# NeuroStimDuino_v3.net
KiCad netlist of a schematic drawn in EAGLE
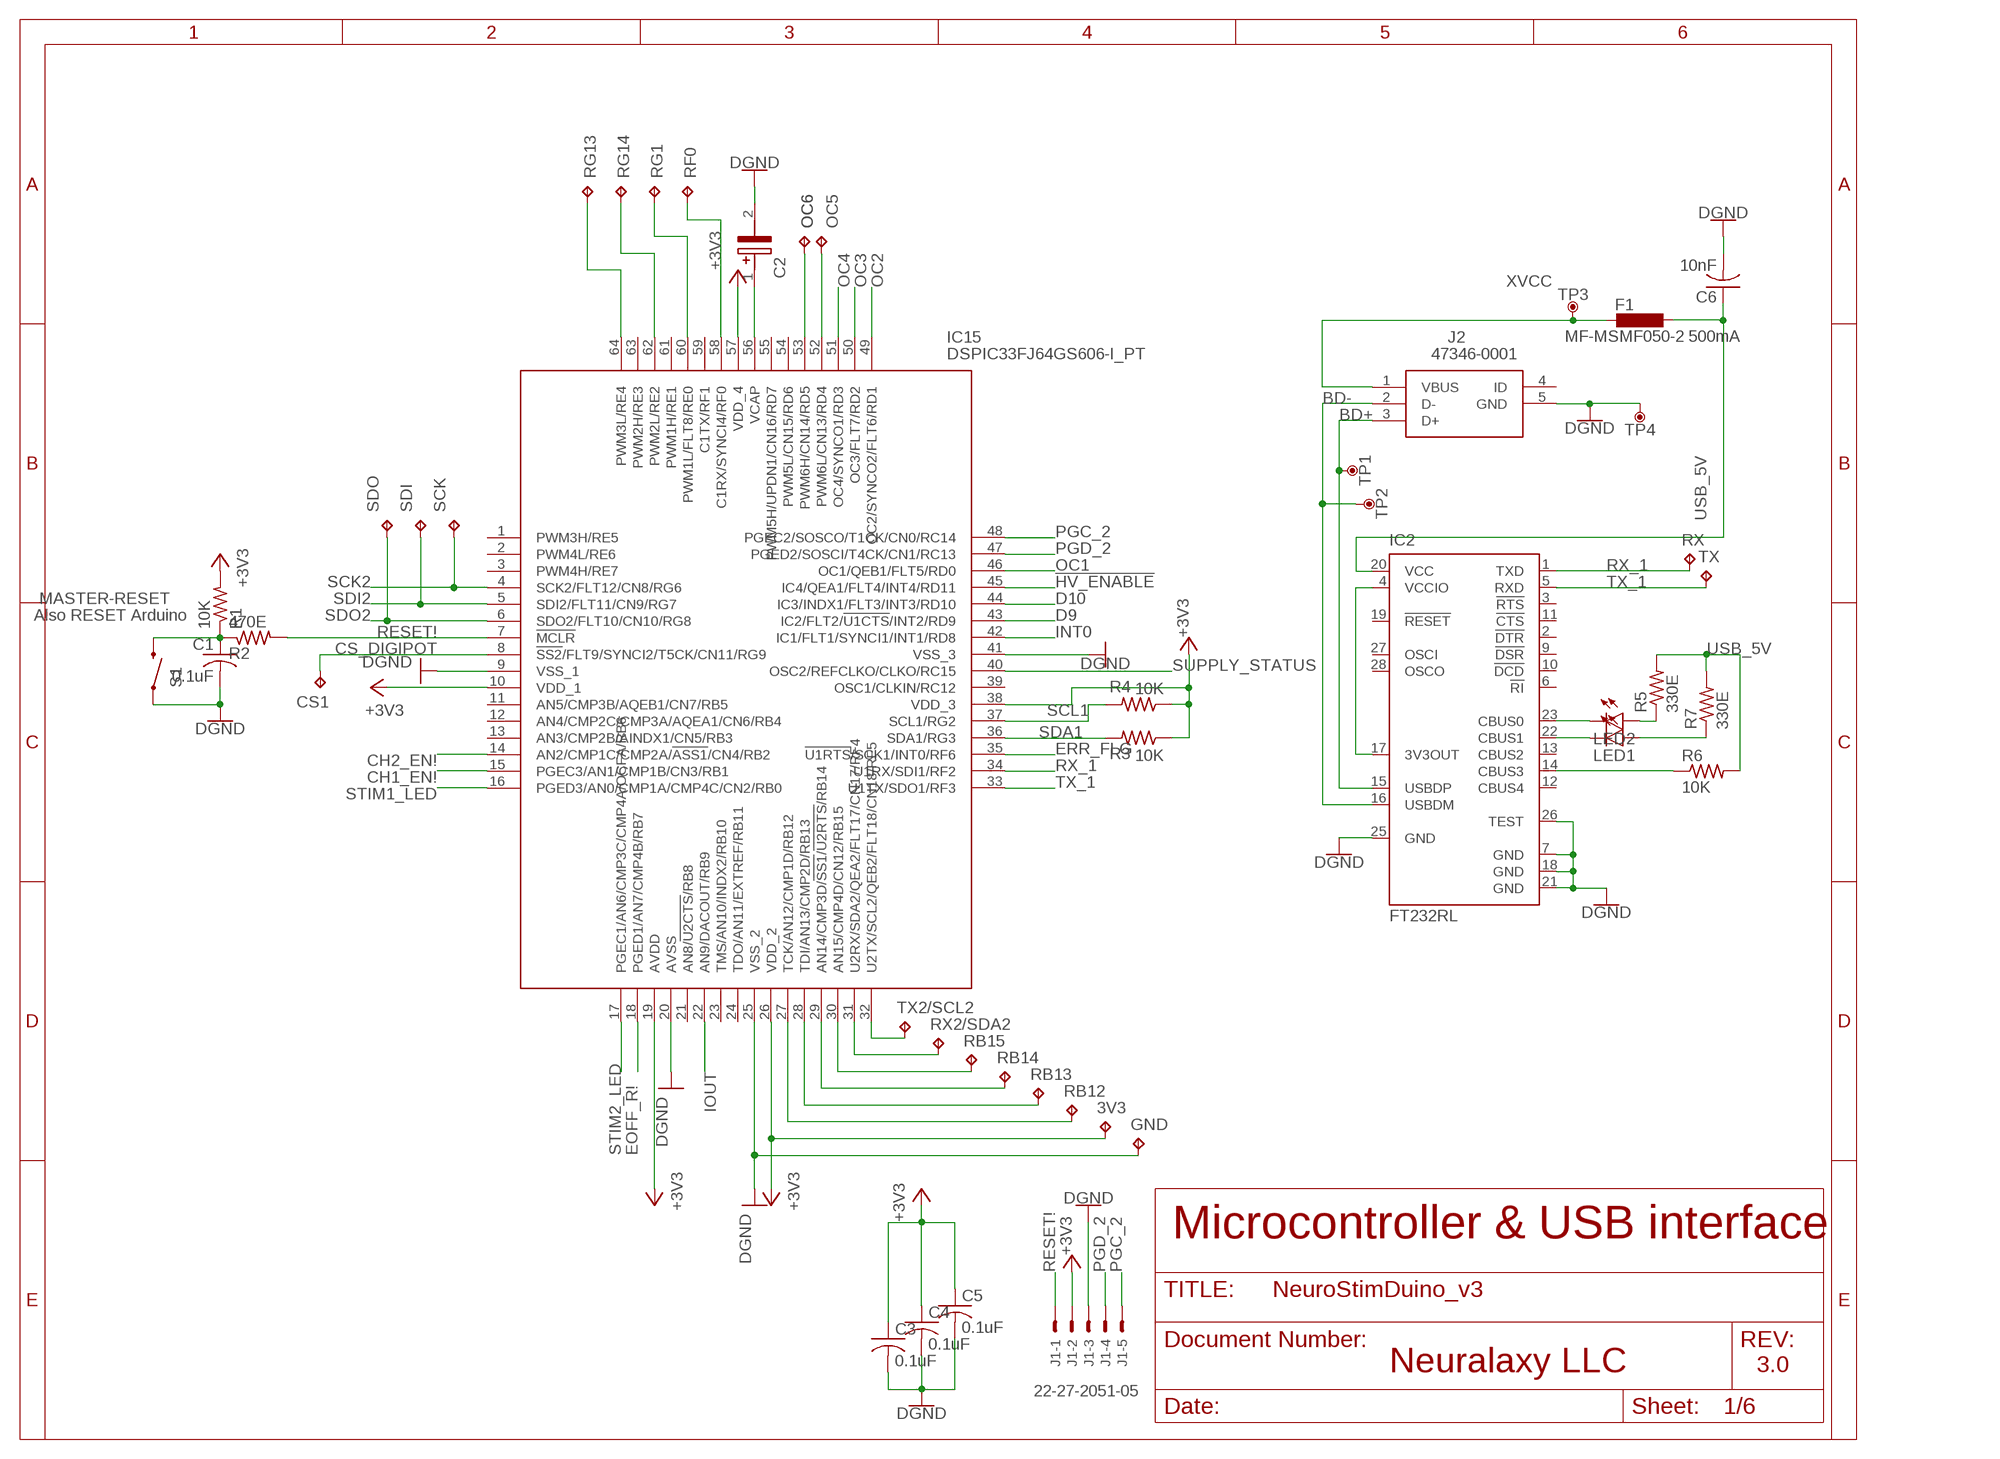
[diagram p0: schematic, sheet 1]
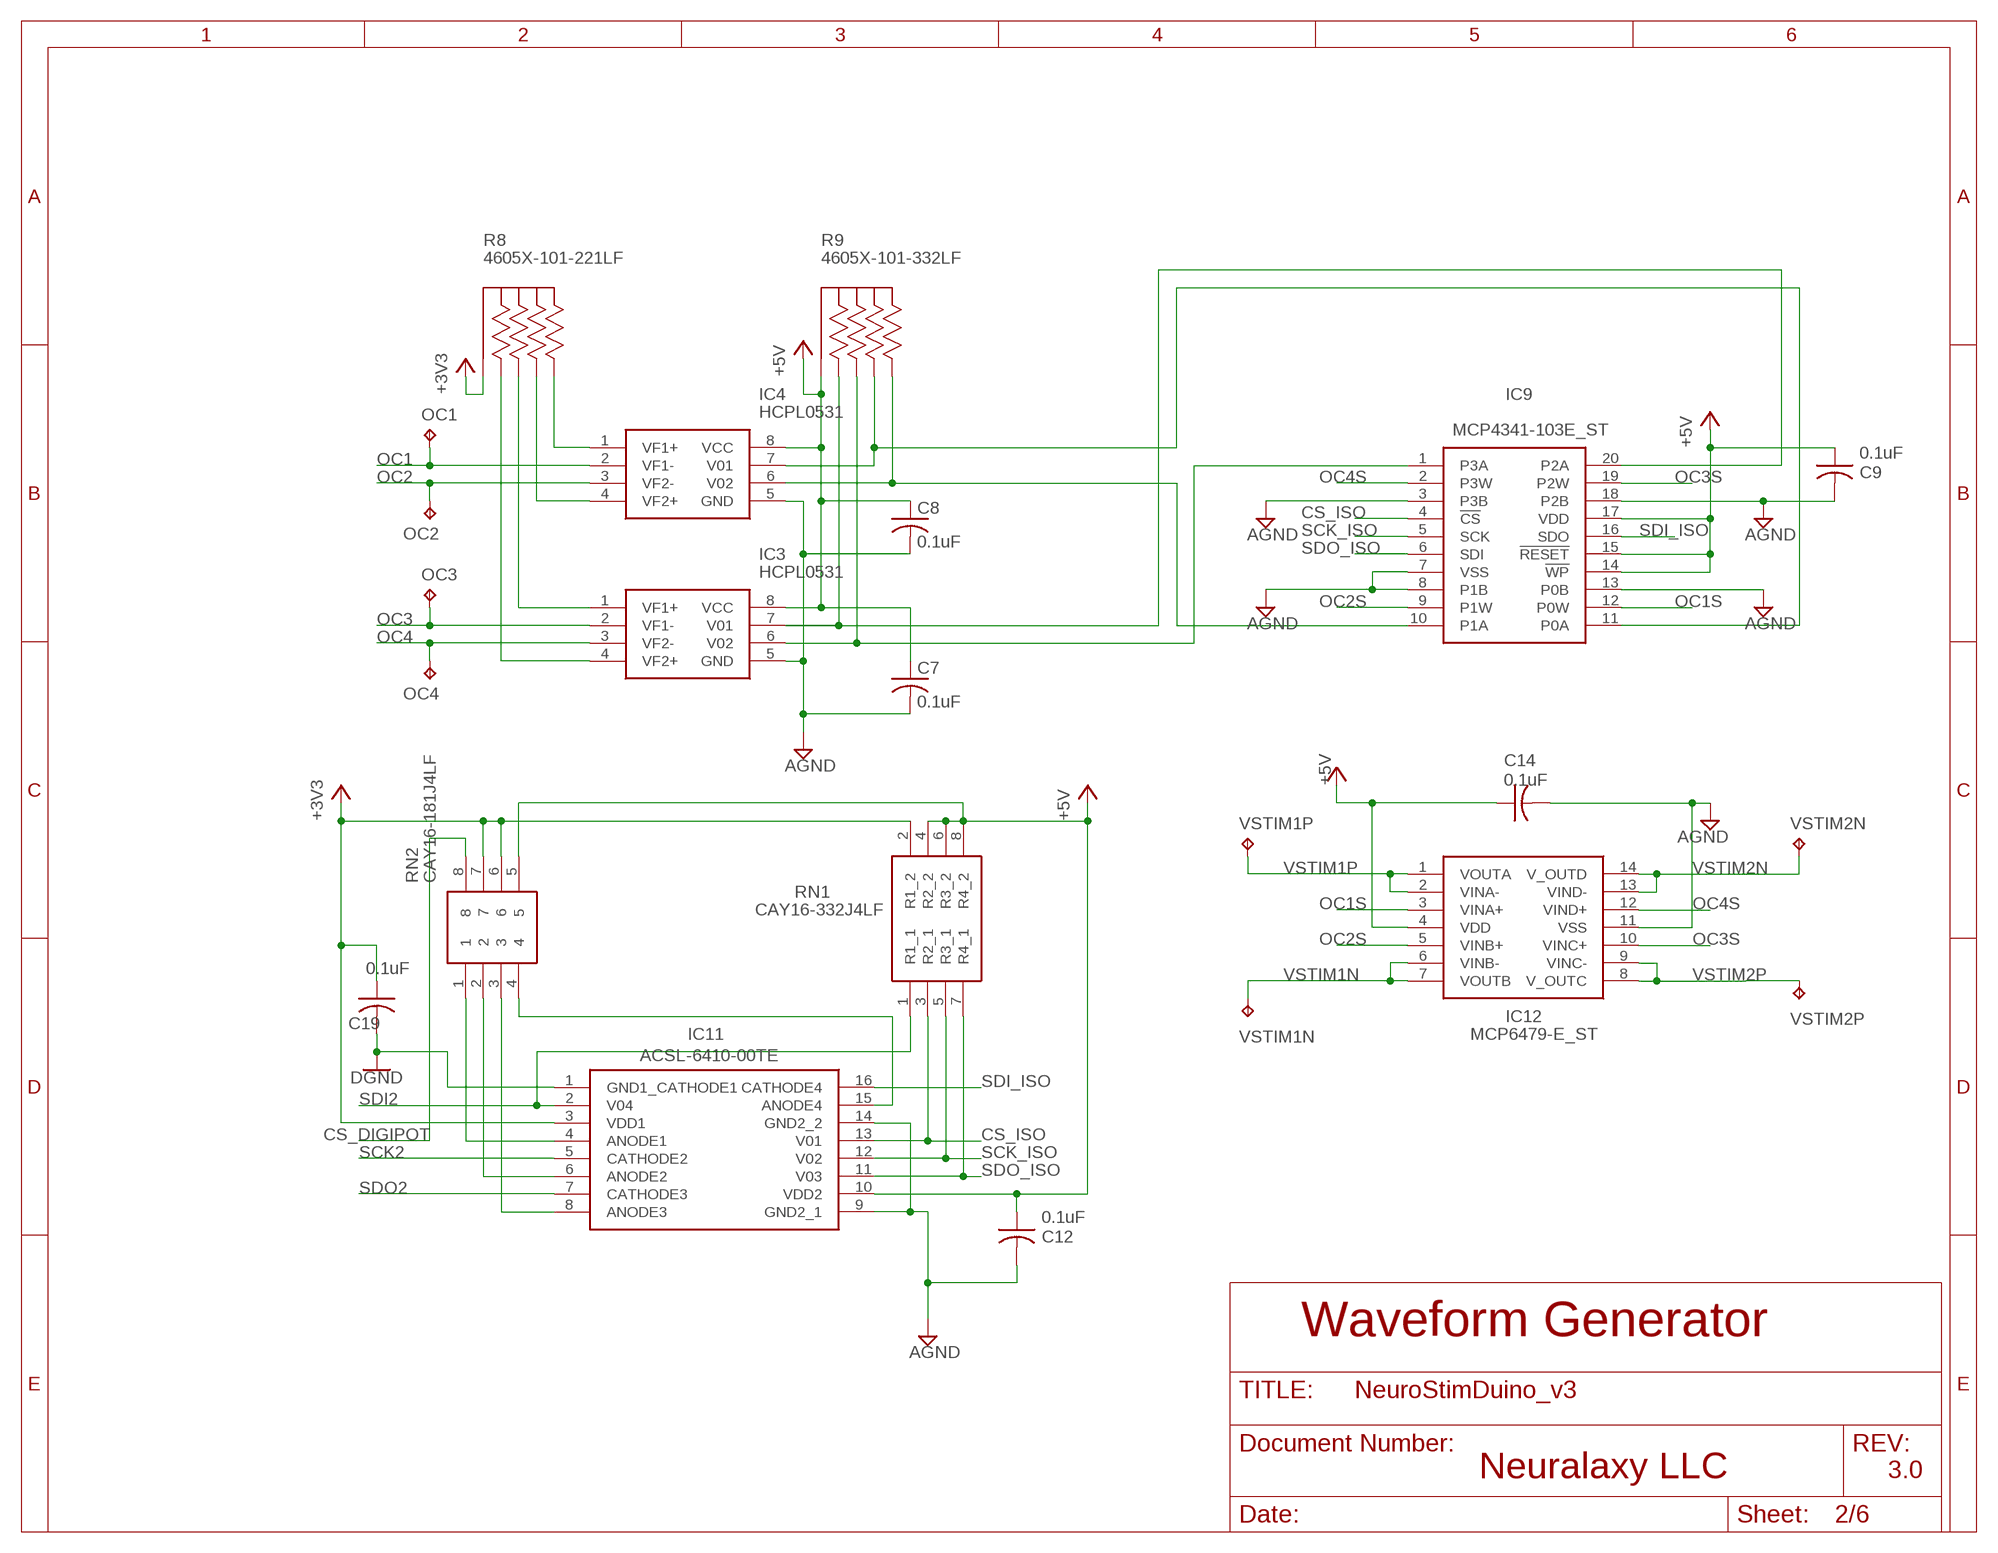
[diagram p1: schematic, sheet 2]
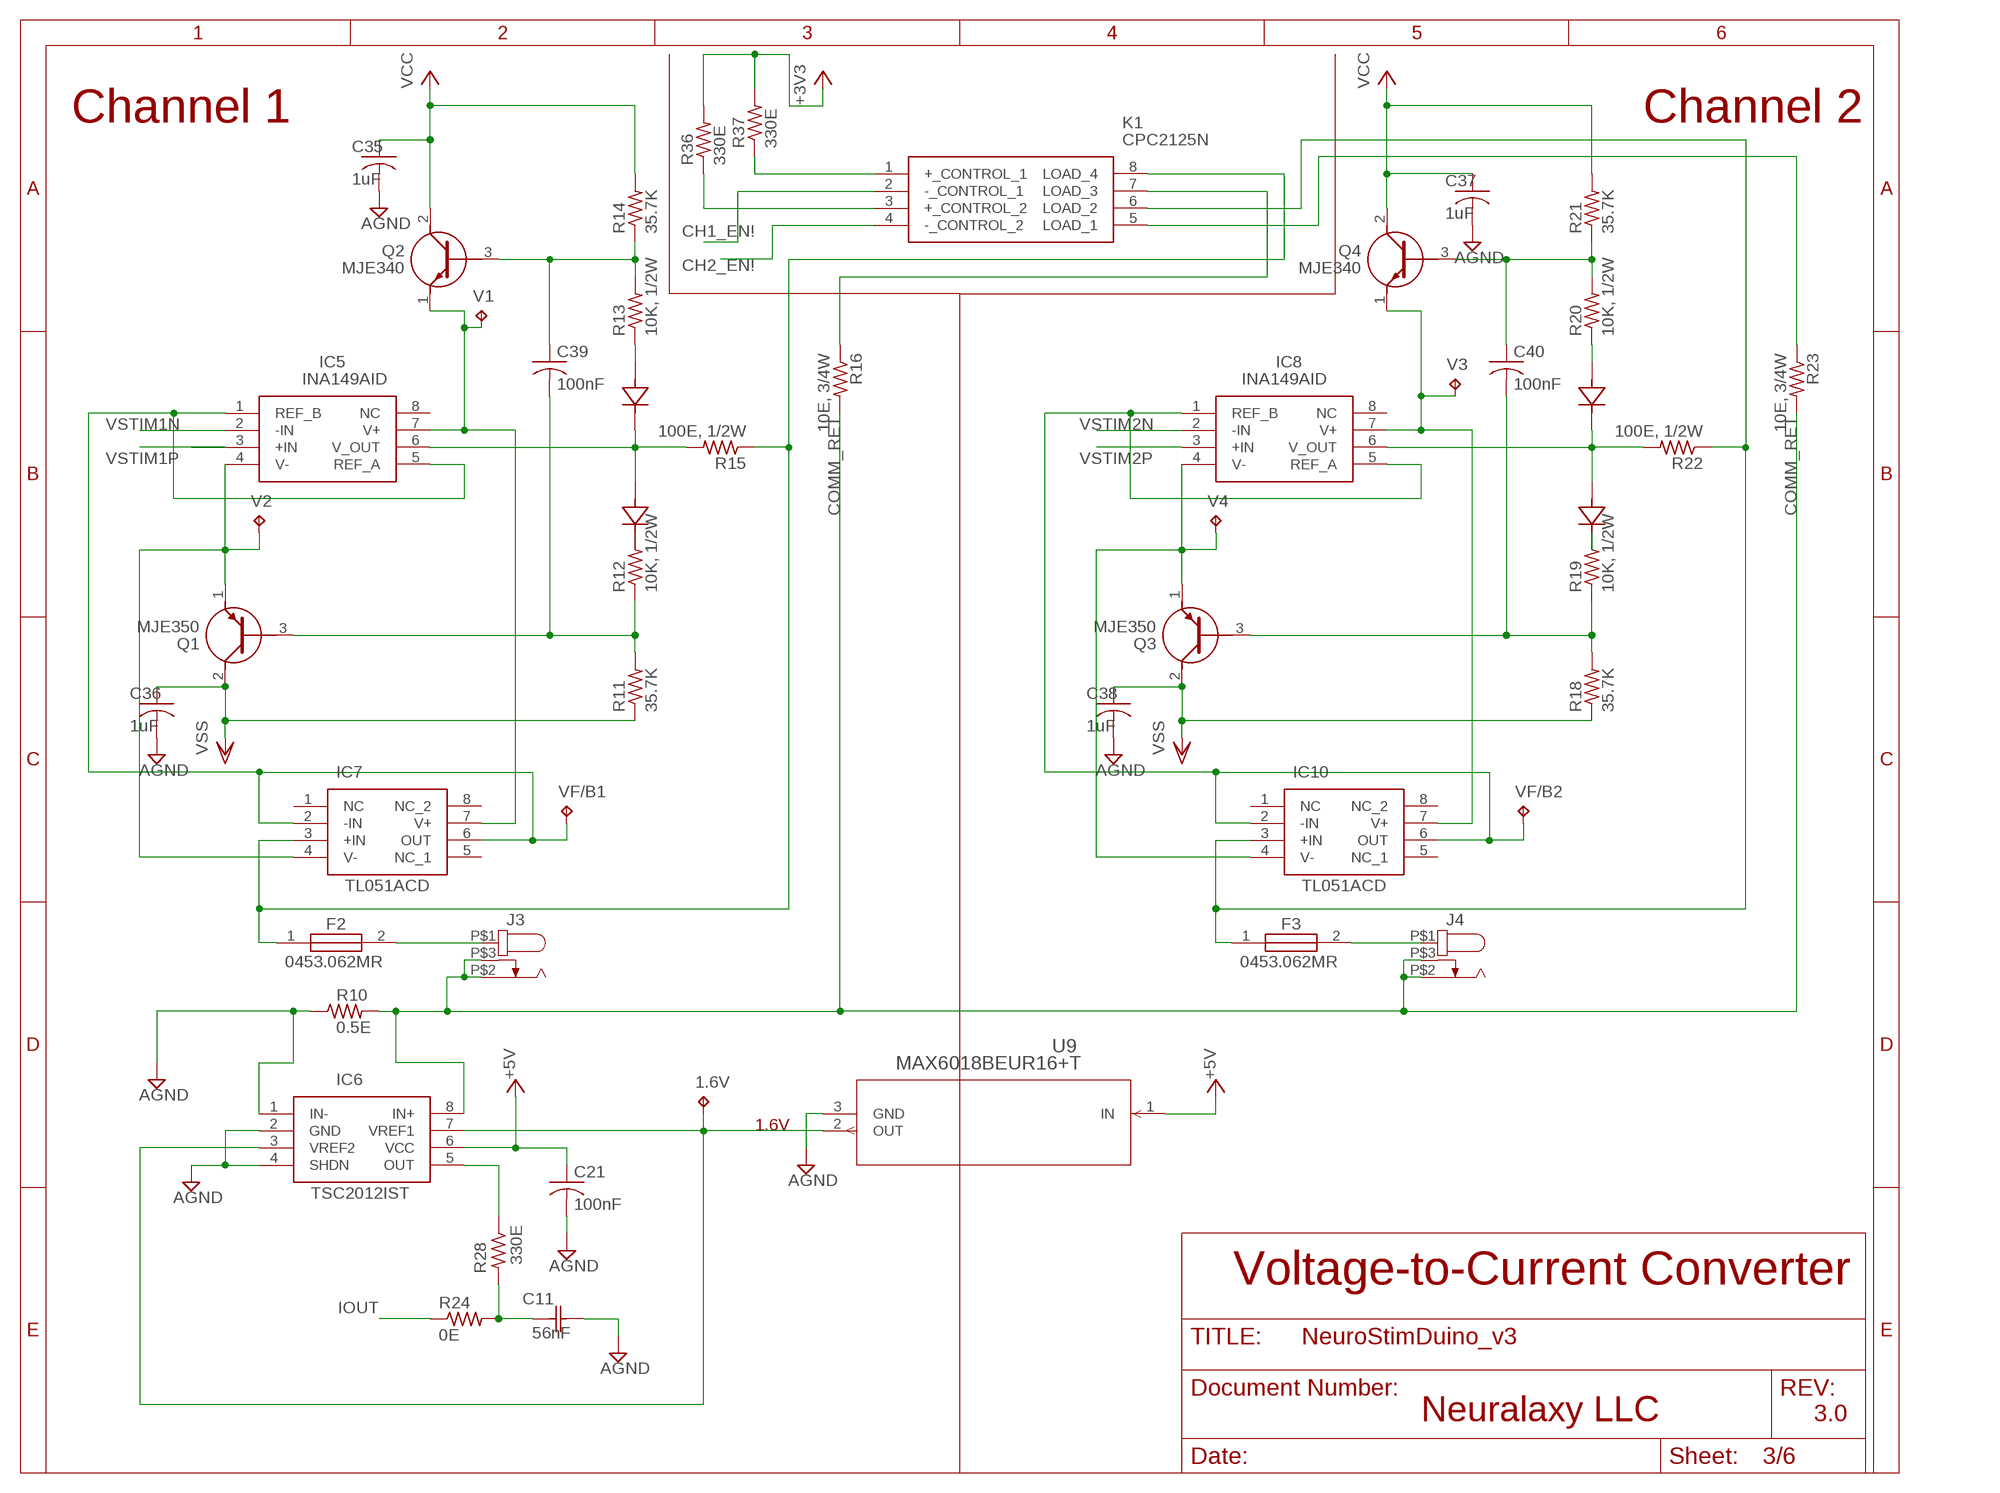
[diagram p2: schematic, sheet 3]
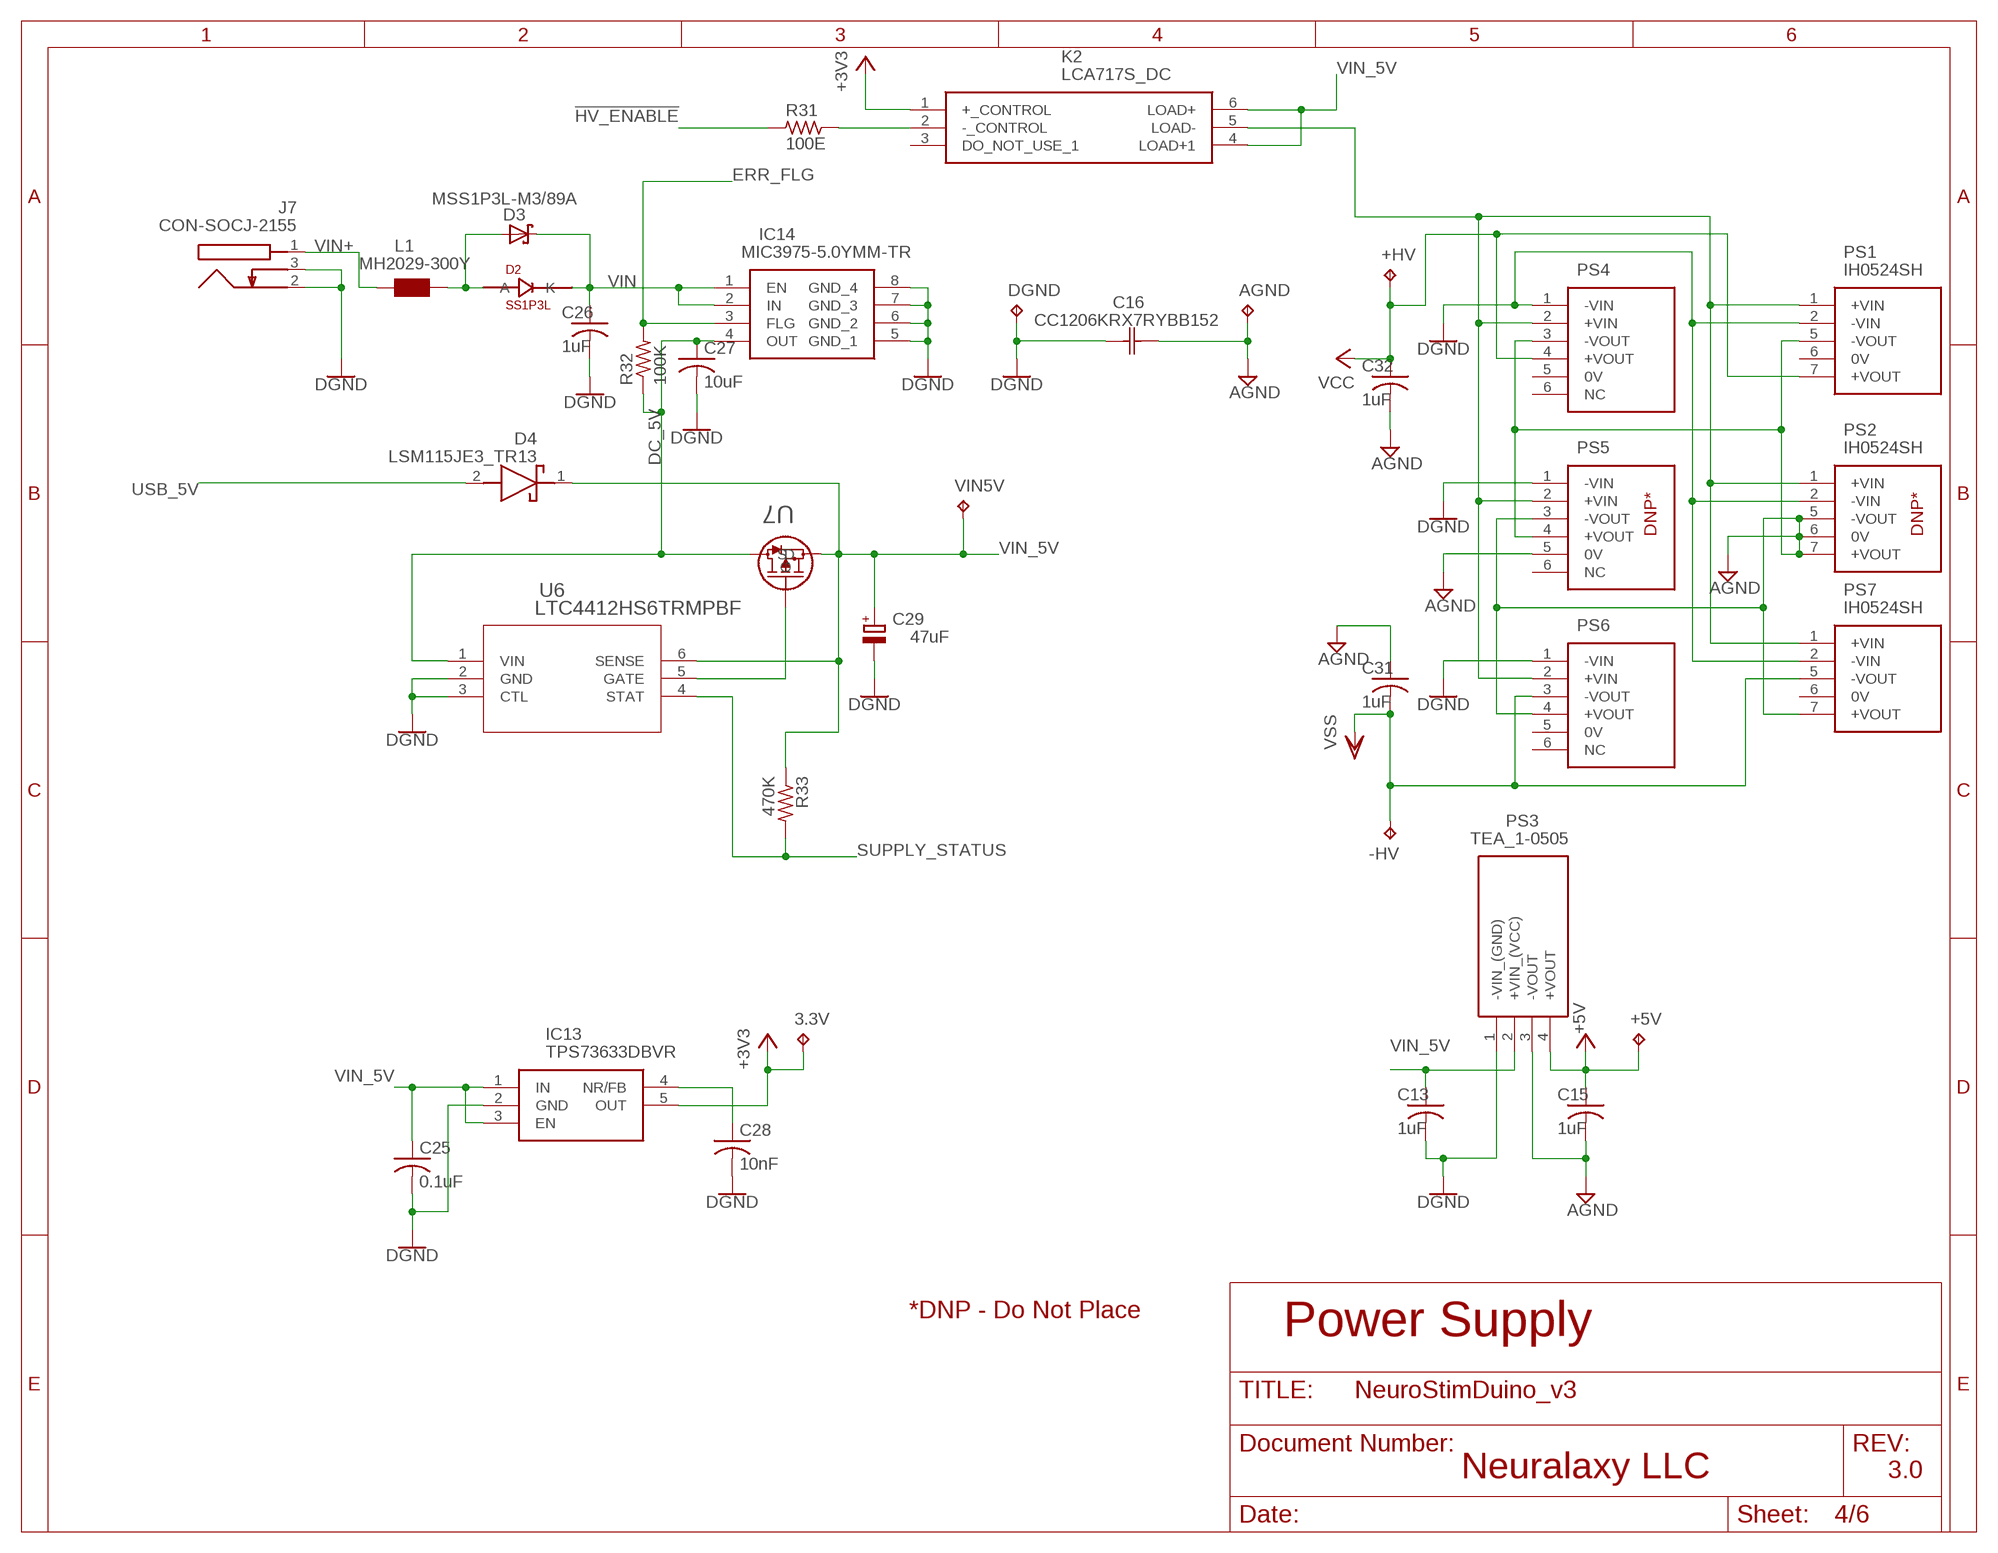
[diagram p3: schematic, sheet 4]
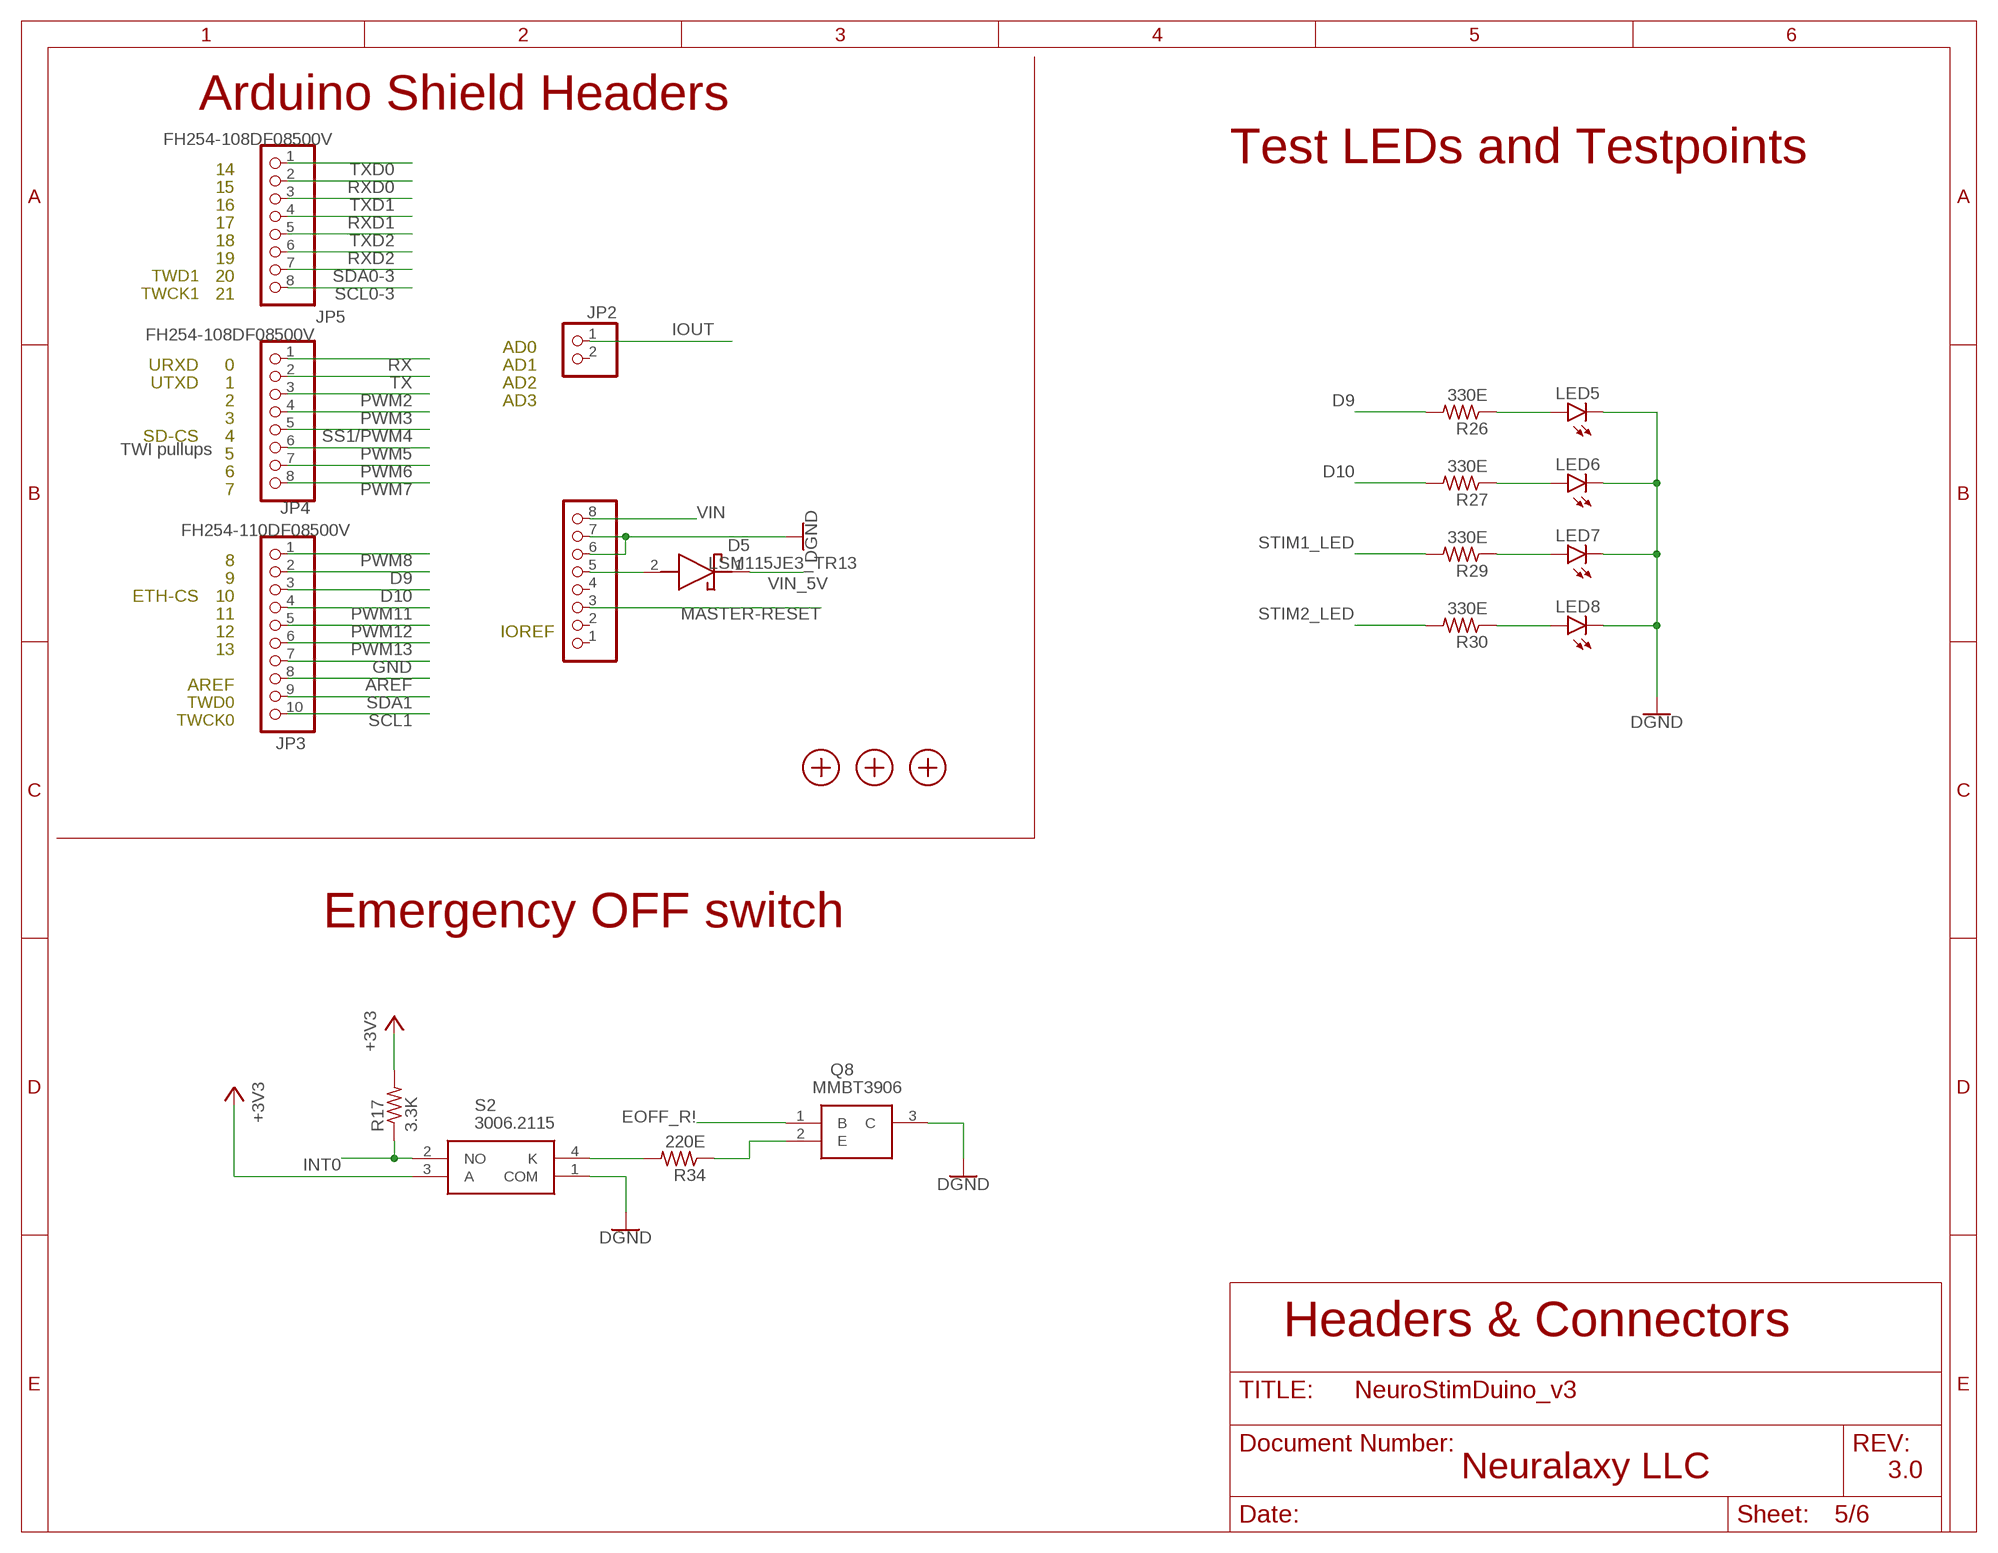
[diagram p4: schematic, sheet 5]
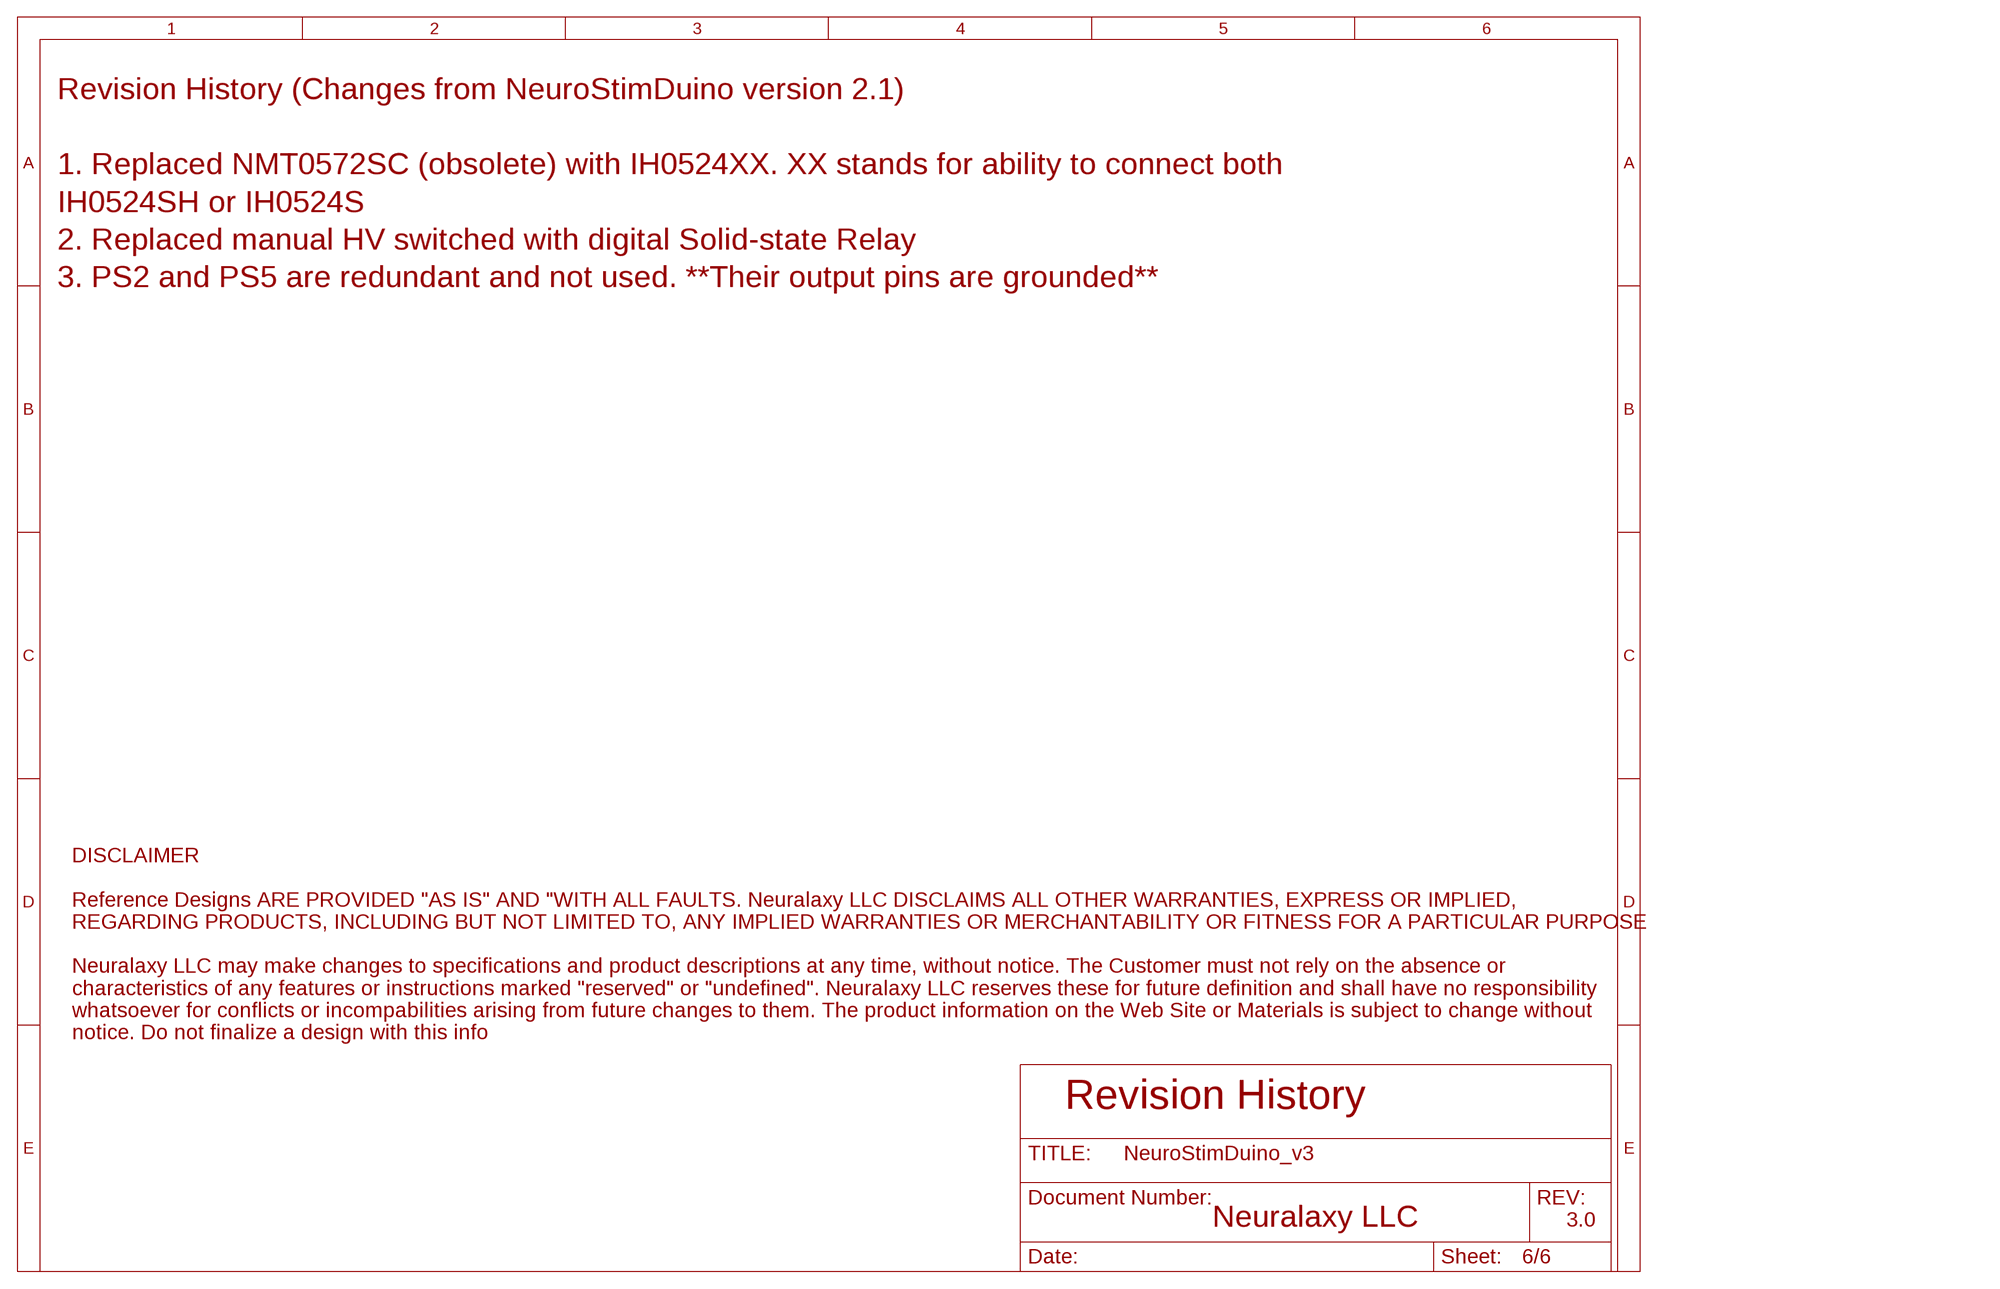
[diagram p5: schematic, sheet 6]

(export (version "E")
  (design (tool "Eeschema 10.0.6"))
  (components
    (comp (ref "1.6V")
      (value "TPTP10R")
      (footprint "eagle-import:TP10R")
      (libsource (lib "eagle-import") (part "TPTP10R"))
    )
    (comp (ref "C11")
      (value "56nF")
      (footprint "eagle-import:CAPC17595_87N_KEM")
      (fields (field (name "MANUFACTURER_PART_NUMBER") "C0603C563J4RACTU"))
      (libsource (lib "eagle-import") (part "C0603C563J4RACTU"))
    )
    (comp (ref "C21")
      (value "100nF")
      (footprint "eagle-import:C1206")
      (libsource (lib "eagle-import") (part "rcl_334_C-USC1206"))
    )
    (comp (ref "C35")
      (value "1uF")
      (footprint "eagle-import:C0805")
      (libsource (lib "eagle-import") (part "rcl_334_C-USC0805"))
    )
    (comp (ref "C36")
      (value "1uF")
      (footprint "eagle-import:C0805")
      (libsource (lib "eagle-import") (part "rcl_334_C-USC0805"))
    )
    (comp (ref "C37")
      (value "1uF")
      (footprint "eagle-import:C0805")
      (libsource (lib "eagle-import") (part "rcl_334_C-USC0805"))
    )
    (comp (ref "C38")
      (value "1uF")
      (footprint "eagle-import:C0805")
      (libsource (lib "eagle-import") (part "rcl_334_C-USC0805"))
    )
    (comp (ref "C39")
      (value "100nF")
      (footprint "eagle-import:C0805K")
      (libsource (lib "eagle-import") (part "rcl_334_C-USC0805K"))
    )
    (comp (ref "C40")
      (value "100nF")
      (footprint "eagle-import:C0805K")
      (libsource (lib "eagle-import") (part "rcl_334_C-USC0805K"))
    )
    (comp (ref "D6")
      (value "GF1J-E3DO-214BA-L")
      (footprint "eagle-import:DO-214BA-L")
      (fields (field (name "MANUFACTURER_PART_NUMBER") "GF1J-E3"))
      (libsource (lib "eagle-import") (part "GF1J-E3DO-214BA-L"))
    )
    (comp (ref "D7")
      (value "GF1J-E3DO-214BA-L")
      (footprint "eagle-import:DO-214BA-L")
      (fields (field (name "MANUFACTURER_PART_NUMBER") "GF1J-E3"))
      (libsource (lib "eagle-import") (part "GF1J-E3DO-214BA-L"))
    )
    (comp (ref "D8")
      (value "GF1J-E3DO-214BA-L")
      (footprint "eagle-import:DO-214BA-L")
      (fields (field (name "MANUFACTURER_PART_NUMBER") "GF1J-E3"))
      (libsource (lib "eagle-import") (part "GF1J-E3DO-214BA-L"))
    )
    (comp (ref "D9")
      (value "GF1J-E3DO-214BA-L")
      (footprint "eagle-import:DO-214BA-L")
      (fields (field (name "MANUFACTURER_PART_NUMBER") "GF1J-E3"))
      (libsource (lib "eagle-import") (part "GF1J-E3DO-214BA-L"))
    )
    (comp (ref "F2")
      (value "0453.062MR")
      (footprint "eagle-import:FUSC6127X294N")
      (libsource (lib "eagle-import") (part "0453.062MR"))
    )
    (comp (ref "F3")
      (value "0453.062MR")
      (footprint "eagle-import:FUSC6127X294N")
      (libsource (lib "eagle-import") (part "0453.062MR"))
    )
    (comp (ref "IC5")
      (value "INA149AID")
      (footprint "eagle-import:SOIC127P600X175-8N")
      (fields (field (name "MOUSER_PART_NUMBER") "595-INA149AID"))
      (libsource (lib "eagle-import") (part "INA149AID"))
    )
    (comp (ref "IC6")
      (value "TSC2012IST")
      (footprint "eagle-import:SOP65P490X110-8N")
      (fields
        (field (name "MANUFACTURER_PART_NUMBER") "TSC2011IST")
        (field (name "MOUSER_PART_NUMBER") "511-TSC2011IST")
      )
      (libsource (lib "eagle-import") (part "TSC2012IST"))
    )
    (comp (ref "IC7")
      (value "OPA140AID")
      (footprint "eagle-import:SOIC127P600X175-8N")
      (fields (field (name "MOUSER_PART_NUMBER") "595-OPA140AID"))
      (libsource (lib "eagle-import") (part "OPA140AID"))
    )
    (comp (ref "IC8")
      (value "INA149AID")
      (footprint "eagle-import:SOIC127P600X175-8N")
      (fields (field (name "MOUSER_PART_NUMBER") "595-INA149AID"))
      (libsource (lib "eagle-import") (part "INA149AID"))
    )
    (comp (ref "IC10")
      (value "OPA140AID")
      (footprint "eagle-import:SOIC127P600X175-8N")
      (fields (field (name "MOUSER_PART_NUMBER") "595-OPA140AID"))
      (libsource (lib "eagle-import") (part "OPA140AID"))
    )
    (comp (ref "J3")
      (value "DC_JACK_081BB-2103300")
      (footprint "eagle-import:081BB-2103300")
      (libsource (lib "eagle-import") (part "DC_JACK_081BB-2103300"))
    )
    (comp (ref "J4")
      (value "DC_JACK_081BB-2103300")
      (footprint "eagle-import:081BB-2103300")
      (libsource (lib "eagle-import") (part "DC_JACK_081BB-2103300"))
    )
    (comp (ref "K1")
      (value "CPC2125N")
      (footprint "eagle-import:SOP254P610X218-8N")
      (fields (field (name "MOUSER_PART_NUMBER") "849-CPC2125N"))
      (libsource (lib "eagle-import") (part "CPC2125N"))
    )
    (comp (ref "Q1")
      (value "MJE350")
      (footprint "eagle-import:TO229P300X760X1364-3P")
      (fields
        (field (name "MANUFACTURER_PART_NUMBER") "MJE350G")
        (field (name "MOUSER_PART_NUMBER") "863-MJE350G")
      )
      (libsource (lib "eagle-import") (part "MJE350"))
    )
    (comp (ref "Q2")
      (value "MJE340")
      (footprint "eagle-import:TO229P290X760X1320-3P")
      (fields (field (name "MOUSER_PART_NUMBER") "511-MJE340"))
      (libsource (lib "eagle-import") (part "MJE340"))
    )
    (comp (ref "Q3")
      (value "MJE350")
      (footprint "eagle-import:TO229P300X760X1364-3P")
      (fields
        (field (name "MANUFACTURER_PART_NUMBER") "MJE350G")
        (field (name "MOUSER_PART_NUMBER") "863-MJE350G")
      )
      (libsource (lib "eagle-import") (part "MJE350"))
    )
    (comp (ref "Q4")
      (value "MJE340")
      (footprint "eagle-import:TO229P290X760X1320-3P")
      (fields (field (name "MOUSER_PART_NUMBER") "511-MJE340"))
      (libsource (lib "eagle-import") (part "MJE340"))
    )
    (comp (ref "R10")
      (value "0.5E")
      (footprint "eagle-import:R1206")
      (libsource (lib "eagle-import") (part "rcl_334_R-US_R1206"))
    )
    (comp (ref "R11")
      (value "35.7K")
      (footprint "eagle-import:R1206")
      (libsource (lib "eagle-import") (part "rcl_334_R-US_R1206"))
    )
    (comp (ref "R12")
      (value "10K, 1/2W")
      (footprint "eagle-import:R1206")
      (libsource (lib "eagle-import") (part "rcl_334_R-US_R1206"))
    )
    (comp (ref "R13")
      (value "10K, 1/2W")
      (footprint "eagle-import:R1206")
      (libsource (lib "eagle-import") (part "rcl_334_R-US_R1206"))
    )
    (comp (ref "R14")
      (value "35.7K")
      (footprint "eagle-import:R1206")
      (libsource (lib "eagle-import") (part "rcl_334_R-US_R1206"))
    )
    (comp (ref "R15")
      (value "100E, 1/2W")
      (footprint "eagle-import:R1206")
      (libsource (lib "eagle-import") (part "rcl_334_R-US_R1206"))
    )
    (comp (ref "R16")
      (value "10E, 3/4W")
      (footprint "eagle-import:R1206")
      (libsource (lib "eagle-import") (part "rcl_334_R-US_R1206"))
    )
    (comp (ref "R18")
      (value "35.7K")
      (footprint "eagle-import:R1206")
      (libsource (lib "eagle-import") (part "rcl_334_R-US_R1206"))
    )
    (comp (ref "R19")
      (value "10K, 1/2W")
      (footprint "eagle-import:R1206")
      (libsource (lib "eagle-import") (part "rcl_334_R-US_R1206"))
    )
    (comp (ref "R20")
      (value "10K, 1/2W")
      (footprint "eagle-import:R1206")
      (libsource (lib "eagle-import") (part "rcl_334_R-US_R1206"))
    )
    (comp (ref "R21")
      (value "35.7K")
      (footprint "eagle-import:R1206")
      (libsource (lib "eagle-import") (part "rcl_334_R-US_R1206"))
    )
    (comp (ref "R22")
      (value "100E, 1/2W")
      (footprint "eagle-import:R1206")
      (libsource (lib "eagle-import") (part "rcl_334_R-US_R1206"))
    )
    (comp (ref "R23")
      (value "10E, 3/4W")
      (footprint "eagle-import:R1206")
      (libsource (lib "eagle-import") (part "rcl_334_R-US_R1206"))
    )
    (comp (ref "R24")
      (value "0E")
      (footprint "eagle-import:R1206")
      (libsource (lib "eagle-import") (part "rcl_334_R-US_R1206"))
    )
    (comp (ref "R28")
      (value "330E")
      (footprint "eagle-import:R0603")
      (libsource (lib "eagle-import") (part "R-US_R0603"))
    )
    (comp (ref "R36")
      (value "330E")
      (footprint "eagle-import:R1206")
      (libsource (lib "eagle-import") (part "R-US_R1206"))
    )
    (comp (ref "R37")
      (value "330E")
      (footprint "eagle-import:R1206")
      (libsource (lib "eagle-import") (part "R-US_R1206"))
    )
    (comp (ref "U9")
      (value "MAX6018BEUR16+T")
      (footprint "eagle-import:21-0051H_MXM")
      (libsource (lib "eagle-import") (part "MAX6018BEUR16+T"))
    )
    (comp (ref "V1")
      (value "TPTP10R")
      (footprint "eagle-import:TP10R")
      (libsource (lib "eagle-import") (part "TPTP10R"))
    )
    (comp (ref "V2")
      (value "TPTP10R")
      (footprint "eagle-import:TP10R")
      (libsource (lib "eagle-import") (part "TPTP10R"))
    )
    (comp (ref "V3")
      (value "TPTP10R")
      (footprint "eagle-import:TP10R")
      (libsource (lib "eagle-import") (part "TPTP10R"))
    )
    (comp (ref "V4")
      (value "TPTP10R")
      (footprint "eagle-import:TP10R")
      (libsource (lib "eagle-import") (part "TPTP10R"))
    )
    (comp (ref "VF/B1")
      (value "TPTP10R")
      (footprint "eagle-import:TP10R")
      (libsource (lib "eagle-import") (part "TPTP10R"))
    )
    (comp (ref "VF/B2")
      (value "TPTP10R")
      (footprint "eagle-import:TP10R")
      (libsource (lib "eagle-import") (part "TPTP10R"))
    )
    (comp (ref "+5V")
      (value "TPTP10R")
      (footprint "eagle-import:TP10R")
      (libsource (lib "eagle-import") (part "TPTP10R"))
    )
    (comp (ref "+HV")
      (value "TPTP10R")
      (footprint "eagle-import:TP10R")
      (libsource (lib "eagle-import") (part "TPTP10R"))
    )
    (comp (ref "-HV")
      (value "TPTP10R")
      (footprint "eagle-import:TP10R")
      (libsource (lib "eagle-import") (part "TPTP10R"))
    )
    (comp (ref "3.3V")
      (value "TPTP10R")
      (footprint "eagle-import:TP10R")
      (libsource (lib "eagle-import") (part "TPTP10R"))
    )
    (comp (ref "AGND")
      (value "TPTP10R")
      (footprint "eagle-import:TP10R")
      (libsource (lib "eagle-import") (part "TPTP10R"))
    )
    (comp (ref "C13")
      (value "1uF")
      (footprint "eagle-import:C0805")
      (libsource (lib "eagle-import") (part "rcl_334_C-USC0805"))
    )
    (comp (ref "C15")
      (value "1uF")
      (footprint "eagle-import:C0805")
      (libsource (lib "eagle-import") (part "rcl_334_C-USC0805"))
    )
    (comp (ref "C16")
      (value "CC1206KRX7RYBB152")
      (footprint "eagle-import:CAP_CC1206_YAG")
      (fields (field (name "COPYRIGHT") "Copyright (C) 2025 Ultra Librarian. All rights reserved."))
      (libsource (lib "eagle-import") (part "CC1206KRX7RYBB152"))
    )
    (comp (ref "C25")
      (value "0.1uF")
      (footprint "eagle-import:C1206")
      (libsource (lib "eagle-import") (part "C-USC1206"))
    )
    (comp (ref "C26")
      (value "1uF")
      (footprint "eagle-import:C0805")
      (libsource (lib "eagle-import") (part "rcl_334_C-USC0805"))
    )
    (comp (ref "C27")
      (value "10uF")
      (footprint "eagle-import:C0805")
      (libsource (lib "eagle-import") (part "rcl_334_C-USC0805"))
    )
    (comp (ref "C28")
      (value "10nF")
      (footprint "eagle-import:C1206")
      (libsource (lib "eagle-import") (part "C-USC1206"))
    )
    (comp (ref "C29")
      (value "47uF")
      (footprint "eagle-import:PANASONIC_D")
      (libsource (lib "eagle-import") (part "0113_47UF"))
    )
    (comp (ref "C31")
      (value "1uF")
      (footprint "eagle-import:C0805")
      (libsource (lib "eagle-import") (part "rcl_334_C-USC0805"))
    )
    (comp (ref "C32")
      (value "1uF")
      (footprint "eagle-import:C0805")
      (libsource (lib "eagle-import") (part "rcl_334_C-USC0805"))
    )
    (comp (ref "D2")
      (value "SS1P3L")
      (footprint "eagle-import:DO220AAL")
      (fields (field (name "PART_NUMBER") "SS1P3L-M3/84A"))
      (libsource (lib "eagle-import") (part "0025_SS1P3L-M3/84A"))
    )
    (comp (ref "D3")
      (value "MSS1P3L-M3/89A")
      (footprint "eagle-import:MICROSMP")
      (libsource (lib "eagle-import") (part "1653_MSS1P3L-M3/89A"))
    )
    (comp (ref "D4")
      (value "LSM115JE3_TR13")
      (footprint "eagle-import:DIOM5436X330N")
      (fields
        (field (name "ARROW_PART_NUMBER") "LSM115JE3/TR13")
        (field (name "MOUSER_PART_NUMBER") "494-LSM115JE3/TR13")
      )
      (libsource (lib "eagle-import") (part "LSM115JE3_TR13"))
    )
    (comp (ref "DGND")
      (value "TPTP10R")
      (footprint "eagle-import:TP10R")
      (libsource (lib "eagle-import") (part "TPTP10R"))
    )
    (comp (ref "IC13")
      (value "TPS73633DBVR")
      (footprint "eagle-import:SOT95P280X145-5N")
      (fields (field (name "MOUSER_PART_NUMBER") "595-TPS73633DBVR"))
      (libsource (lib "eagle-import") (part "TPS73633DBVR"))
    )
    (comp (ref "IC14")
      (value "MIC3975-5.0YMM-TR")
      (footprint "eagle-import:SOP65P490X109-8N")
      (libsource (lib "eagle-import") (part "MIC3975-5.0YMM-TR"))
    )
    (comp (ref "J7")
      (value "CON-SOCJ-2155")
      (footprint "eagle-import:CONSOCJ2155")
      (fields (field (name "MOUSER_PART_NUMBER") "992-CON-SOCJ-2155"))
      (libsource (lib "eagle-import") (part "CON-SOCJ-2155"))
    )
    (comp (ref "K2")
      (value "LCA717S_DC")
      (footprint "eagle-import:SOP254P952X470-6N")
      (fields
        (field (name "MANUFACTURER_PART_NUMBER") "LCA717S")
        (field (name "MOUSER_PART_NUMBER") "849-LCA717S")
      )
      (libsource (lib "eagle-import") (part "LCA717S_DC"))
    )
    (comp (ref "L1")
      (value "MH2029-300Y")
      (footprint "eagle-import:0805")
      (fields (field (name "PART_NUMBER") "BLM21PG300SN1D_/_MH2029-300Y"))
      (libsource (lib "eagle-import") (part "0001_BLM21PG300SN1D_/_MH2029-300Y"))
    )
    (comp (ref "PS1")
      (value "IH0524SH")
      (footprint "eagle-import:IH0524SH")
      (fields (field (name "MOUSER_PART_NUMBER") "209-IH0524SH"))
      (libsource (lib "eagle-import") (part "IH0524SH"))
    )
    (comp (ref "PS2")
      (value "IH0524SH")
      (footprint "eagle-import:IH0524SH")
      (fields (field (name "MOUSER_PART_NUMBER") "209-IH0524SH"))
      (libsource (lib "eagle-import") (part "IH0524SH"))
    )
    (comp (ref "PS3")
      (value "TEA_1-0505")
      (footprint "eagle-import:TEA10505")
      (fields
        (field (name "MANUFACTURER_PART_NUMBER") "TEA 1-0505")
        (field (name "MOUSER_PART_NUMBER") "495-TEA1-0505")
      )
      (libsource (lib "eagle-import") (part "TEA_1-0505"))
    )
    (comp (ref "PS4")
      (value "IH0524D")
      (footprint "eagle-import:IH0524D")
      (libsource (lib "eagle-import") (part "IH0524D"))
    )
    (comp (ref "PS5")
      (value "IH0524D")
      (footprint "eagle-import:IH0524D")
      (libsource (lib "eagle-import") (part "IH0524D"))
    )
    (comp (ref "PS6")
      (value "IH0524D")
      (footprint "eagle-import:IH0524D")
      (libsource (lib "eagle-import") (part "IH0524D"))
    )
    (comp (ref "PS7")
      (value "IH0524SH")
      (footprint "eagle-import:IH0524SH")
      (fields (field (name "MOUSER_PART_NUMBER") "209-IH0524SH"))
      (libsource (lib "eagle-import") (part "IH0524SH"))
    )
    (comp (ref "R31")
      (value "100E")
      (footprint "eagle-import:R0805")
      (libsource (lib "eagle-import") (part "R_0805"))
    )
    (comp (ref "R32")
      (value "100K")
      (footprint "eagle-import:R1206")
      (libsource (lib "eagle-import") (part "rcl_334_R-US_R1206"))
    )
    (comp (ref "R33")
      (value "470K")
      (footprint "eagle-import:R1206")
      (libsource (lib "eagle-import") (part "rcl_334_R-US_R1206"))
    )
    (comp (ref "U6")
      (value "LTC4412HS6TRMPBF")
      (footprint "eagle-import:TSOT-23_S6_ADI")
      (fields
        (field (name "MANUFACTURER_PART_NUMBER") "LTC4412HS6#TRMPBF")
        (field (name "COPYRIGHT") "Copyright (C) 2018 Accelerated Designs. All rights reserved")
      )
      (libsource (lib "eagle-import") (part "LTC4412HS6TRMPBF"))
    )
    (comp (ref "U7")
      (value "PMV48XP,215TO-236_SOT23_NEX-L")
      (footprint "eagle-import:TO-236_SOT23_NEX-L")
      (fields
        (field (name "MANUFACTURER_PART_NUMBER") "PMV48XP,215")
        (field (name "COPYRIGHT") "Copyright (C) 2018 Accelerated Designs. All rights reserved")
      )
      (libsource (lib "eagle-import") (part "PMV48XP,215TO-236_SOT23_NEX-L"))
    )
    (comp (ref "VIN5V")
      (value "TPTP10R")
      (footprint "eagle-import:TP10R")
      (libsource (lib "eagle-import") (part "TPTP10R"))
    )
    (comp (ref "C7")
      (value "0.1uF")
      (footprint "eagle-import:C1206")
      (libsource (lib "eagle-import") (part "rcl_334_C-USC1206"))
    )
    (comp (ref "C8")
      (value "0.1uF")
      (footprint "eagle-import:C1206")
      (libsource (lib "eagle-import") (part "rcl_334_C-USC1206"))
    )
    (comp (ref "C9")
      (value "0.1uF")
      (footprint "eagle-import:C1206")
      (libsource (lib "eagle-import") (part "rcl_334_C-USC1206"))
    )
    (comp (ref "C12")
      (value "0.1uF")
      (footprint "eagle-import:C1206")
      (libsource (lib "eagle-import") (part "rcl_334_C-USC1206"))
    )
    (comp (ref "C14")
      (value "0.1uF")
      (footprint "eagle-import:C1206")
      (libsource (lib "eagle-import") (part "rcl_334_C-USC1206"))
    )
    (comp (ref "C19")
      (value "0.1uF")
      (footprint "eagle-import:C1206")
      (libsource (lib "eagle-import") (part "rcl_334_C-USC1206"))
    )
    (comp (ref "IC3")
      (value "HCPL0531")
      (footprint "eagle-import:SOIC127P594X363-8N")
      (fields (field (name "MOUSER_PART_NUMBER") "512-HCPL0531"))
      (libsource (lib "eagle-import") (part "HCPL0531"))
    )
    (comp (ref "IC4")
      (value "HCPL0531")
      (footprint "eagle-import:SOIC127P594X363-8N")
      (fields (field (name "MOUSER_PART_NUMBER") "512-HCPL0531"))
      (libsource (lib "eagle-import") (part "HCPL0531"))
    )
    (comp (ref "IC9")
      (value "MCP4341-103E_ST")
      (footprint "eagle-import:SOP65P640X120-20N")
      (fields
        (field (name "MANUFACTURER_PART_NUMBER") "MCP4341-103E/ST")
        (field (name "MOUSER_PART_NUMBER") "579-MCP4341103E/ST")
      )
      (libsource (lib "eagle-import") (part "MCP4341-103E_ST"))
    )
    (comp (ref "IC11")
      (value "ACSL-6410-00TE")
      (footprint "eagle-import:SOIC127P599X152-16N")
      (fields (field (name "MOUSER_PART_NUMBER") "630-ACSL-6410-00TE"))
      (libsource (lib "eagle-import") (part "ACSL-6410-00TE"))
    )
    (comp (ref "IC12")
      (value "MCP6479-E_ST")
      (footprint "eagle-import:SOP65P640X120-14N")
      (fields
        (field (name "MANUFACTURER_PART_NUMBER") "MCP6479-E/ST")
        (field (name "MOUSER_PART_NUMBER") "579-MCP6479-E/ST")
      )
      (libsource (lib "eagle-import") (part "MCP6479-E_ST"))
    )
    (comp (ref "OC1")
      (value "TPTP08R")
      (footprint "eagle-import:TP08R")
      (libsource (lib "eagle-import") (part "TPTP08R"))
    )
    (comp (ref "OC2")
      (value "TPTP08R")
      (footprint "eagle-import:TP08R")
      (libsource (lib "eagle-import") (part "TPTP08R"))
    )
    (comp (ref "OC3")
      (value "TPTP10R")
      (footprint "eagle-import:TP10R")
      (libsource (lib "eagle-import") (part "TPTP10R"))
    )
    (comp (ref "OC4")
      (value "TPTP10R")
      (footprint "eagle-import:TP10R")
      (libsource (lib "eagle-import") (part "TPTP10R"))
    )
    (comp (ref "R8")
      (value "4605X-101-221LF")
      (footprint "eagle-import:BO_4605X")
      (fields (field (name "MANUFACTURER_PART_NUMBER") "4605X-101-222LF"))
      (libsource (lib "eagle-import") (part "4605X-101-221LF"))
    )
    (comp (ref "R9")
      (value "4605X-101-332LF")
      (footprint "eagle-import:BO_4605X")
      (fields (field (name "MANUFACTURER_PART_NUMBER") "4605X-101-222LF"))
      (libsource (lib "eagle-import") (part "4605X-101-332LF"))
    )
    (comp (ref "RN1")
      (value "CAY16-332J4LF")
      (footprint "eagle-import:CAY16-J4")
      (fields (field (name "MOUSER_PART_NUMBER") "652-CAY16-332J4LF"))
      (libsource (lib "eagle-import") (part "CAY16-332J4LF"))
    )
    (comp (ref "RN2")
      (value "CAY16-181J4LF")
      (footprint "eagle-import:CAY16181J4LF")
      (fields (field (name "MOUSER_PART_NUMBER") "652-CAY16-181J4LF"))
      (libsource (lib "eagle-import") (part "CAY16-181J4LF"))
    )
    (comp (ref "VSTIM1N")
      (value "TPTP08R")
      (footprint "eagle-import:TP08R")
      (libsource (lib "eagle-import") (part "TPTP08R"))
    )
    (comp (ref "VSTIM1P")
      (value "TPTP08R")
      (footprint "eagle-import:TP08R")
      (libsource (lib "eagle-import") (part "TPTP08R"))
    )
    (comp (ref "VSTIM2N")
      (value "TPTP08R")
      (footprint "eagle-import:TP08R")
      (libsource (lib "eagle-import") (part "TPTP08R"))
    )
    (comp (ref "VSTIM2P")
      (value "TPTP08R")
      (footprint "eagle-import:TP08R")
      (libsource (lib "eagle-import") (part "TPTP08R"))
    )
    (comp (ref "D5")
      (value "LSM115JE3_TR13")
      (footprint "eagle-import:DIOM5436X330N")
      (fields
        (field (name "ARROW_PART_NUMBER") "LSM115JE3/TR13")
        (field (name "MOUSER_PART_NUMBER") "494-LSM115JE3/TR13")
      )
      (libsource (lib "eagle-import") (part "LSM115JE3_TR13"))
    )
    (comp (ref "JP2")
      (value "PINHD-1X2")
      (footprint "eagle-import:1X02")
      (libsource (lib "eagle-import") (part "PINHD-1X2"))
    )
    (comp (ref "JP3")
      (value "FH254-110DF08500V")
      (footprint "eagle-import:1X10")
      (fields (field (name "PART_NUMBER") "20TW-537"))
      (libsource (lib "eagle-import") (part "1684_20TW-537"))
    )
    (comp (ref "JP4")
      (value "FH254-108DF08500V")
      (footprint "eagle-import:1X08")
      (fields (field (name "PART_NUMBER") "20TW-536"))
      (libsource (lib "eagle-import") (part "1683_20TW-536"))
    )
    (comp (ref "JP5")
      (value "FH254-108DF08500V")
      (footprint "eagle-import:1X08")
      (fields (field (name "PART_NUMBER") "20TW-536"))
      (libsource (lib "eagle-import") (part "1683_20TW-536"))
    )
    (comp (ref "JP6")
      (value "FH254-108DF08500V")
      (footprint "eagle-import:1X08")
      (fields (field (name "PART_NUMBER") "20TW-536"))
      (libsource (lib "eagle-import") (part "1683_20TW-536"))
    )
    (comp (ref "LED5")
      (value "LEDCHIPLED_1206")
      (footprint "eagle-import:CHIPLED_1206")
      (libsource (lib "eagle-import") (part "LEDCHIPLED_1206"))
    )
    (comp (ref "LED6")
      (value "LEDCHIPLED_1206")
      (footprint "eagle-import:CHIPLED_1206")
      (libsource (lib "eagle-import") (part "LEDCHIPLED_1206"))
    )
    (comp (ref "LED7")
      (value "LEDCHIPLED_1206")
      (footprint "eagle-import:CHIPLED_1206")
      (libsource (lib "eagle-import") (part "LEDCHIPLED_1206"))
    )
    (comp (ref "LED8")
      (value "LEDCHIPLED_1206")
      (footprint "eagle-import:CHIPLED_1206")
      (libsource (lib "eagle-import") (part "LEDCHIPLED_1206"))
    )
    (comp (ref "Q8")
      (value "MMBT3906")
      (footprint "eagle-import:SOT95P240X120-3N")
      (fields (field (name "MOUSER_PART_NUMBER") "512-MMBT3906"))
      (libsource (lib "eagle-import") (part "MMBT3906"))
    )
    (comp (ref "R17")
      (value "3.3K")
      (footprint "eagle-import:R1206")
      (libsource (lib "eagle-import") (part "rcl_334_R-US_R1206"))
    )
    (comp (ref "R26")
      (value "330E")
      (footprint "eagle-import:R0603")
      (libsource (lib "eagle-import") (part "R-US_R0603"))
    )
    (comp (ref "R27")
      (value "330E")
      (footprint "eagle-import:R0603")
      (libsource (lib "eagle-import") (part "R-US_R0603"))
    )
    (comp (ref "R29")
      (value "330E")
      (footprint "eagle-import:R0603")
      (libsource (lib "eagle-import") (part "R-US_R0603"))
    )
    (comp (ref "R30")
      (value "330E")
      (footprint "eagle-import:R0603")
      (libsource (lib "eagle-import") (part "R-US_R0603"))
    )
    (comp (ref "R34")
      (value "220E")
      (footprint "eagle-import:R1206")
      (libsource (lib "eagle-import") (part "rcl_334_R-US_R1206"))
    )
    (comp (ref "S2")
      (value "3006.2115")
      (footprint "eagle-import:30062115")
      (fields (field (name "MOUSER_PART_NUMBER") "979-3006.2115"))
      (libsource (lib "eagle-import") (part "3006.2115"))
    )
    (comp (ref "U$1")
      (value "FIDUCIALMOUNT")
      (footprint "eagle-import:FIDUCIA-MOUNT")
      (libsource (lib "eagle-import") (part "FIDUCIALMOUNT"))
    )
    (comp (ref "U$2")
      (value "FIDUCIALMOUNT")
      (footprint "eagle-import:FIDUCIA-MOUNT")
      (libsource (lib "eagle-import") (part "FIDUCIALMOUNT"))
    )
    (comp (ref "U$3")
      (value "FIDUCIALMOUNT")
      (footprint "eagle-import:FIDUCIA-MOUNT")
      (libsource (lib "eagle-import") (part "FIDUCIALMOUNT"))
    )
    (comp (ref "/OC5")
      (value "TPTP08R")
      (footprint "eagle-import:TP08R")
      (libsource (lib "eagle-import") (part "TPTP08R"))
    )
    (comp (ref "3V3")
      (value "TPTP08R")
      (footprint "eagle-import:TP08R")
      (libsource (lib "eagle-import") (part "TPTP08R"))
    )
    (comp (ref "C1")
      (value "0.1uF")
      (footprint "eagle-import:C0805")
      (libsource (lib "eagle-import") (part "C-USC0805"))
    )
    (comp (ref "C2")
      (value "F971C475MAAHT3")
      (footprint "eagle-import:CAPPM3216X180N")
      (fields (field (name "MOUSER_PART_NUMBER") "581-F971C475MAAHT3"))
      (libsource (lib "eagle-import") (part "F971C475MAAHT3"))
    )
    (comp (ref "C3")
      (value "0.1uF")
      (footprint "eagle-import:C1206")
      (libsource (lib "eagle-import") (part "C-USC1206"))
    )
    (comp (ref "C4")
      (value "0.1uF")
      (footprint "eagle-import:C1206")
      (libsource (lib "eagle-import") (part "C-USC1206"))
    )
    (comp (ref "C5")
      (value "0.1uF")
      (footprint "eagle-import:C1206")
      (libsource (lib "eagle-import") (part "C-USC1206"))
    )
    (comp (ref "C6")
      (value "10nF")
      (footprint "eagle-import:C1206")
      (libsource (lib "eagle-import") (part "rcl_334_C-USC1206"))
    )
    (comp (ref "CS1")
      (value "TPTP08R")
      (footprint "eagle-import:TP08R")
      (libsource (lib "eagle-import") (part "TPTP08R"))
    )
    (comp (ref "F1")
      (value "MF-MSMF050-2 500mA")
      (footprint "eagle-import:L1812")
      (fields (field (name "PART_NUMBER") "MF-MSMF050-2"))
      (libsource (lib "eagle-import") (part "0002_MF-MSMF050-2"))
    )
    (comp (ref "GND")
      (value "TPTP08R")
      (footprint "eagle-import:TP08R")
      (libsource (lib "eagle-import") (part "TPTP08R"))
    )
    (comp (ref "IC2")
      (value "FT232RL")
      (footprint "eagle-import:SSOP28")
      (libsource (lib "eagle-import") (part "FT232RL"))
    )
    (comp (ref "IC15")
      (value "DSPIC33FJ64GS606-I_PT")
      (footprint "eagle-import:QFP50P1200X1200X120-64N")
      (fields
        (field (name "MANUFACTURER_PART_NUMBER") "DSPIC33FJ64GS606-I/PT")
        (field (name "MOUSER_PART_NUMBER") "579-33FJ64GS606-I/PT")
      )
      (libsource (lib "eagle-import") (part "DSPIC33FJ64GS606-I_PT"))
    )
    (comp (ref "J1")
      (value "22-27-2051-05")
      (footprint "eagle-import:6410-05")
      (fields (field (name "MF") "MOLEX"))
      (libsource (lib "eagle-import") (part "22-?-0527-2051"))
    )
    (comp (ref "J2")
      (value "47346-0001")
      (footprint "eagle-import:47346-0001")
      (fields (field (name "MOUSER_PART_NUMBER") "538-47346-0001"))
      (libsource (lib "eagle-import") (part "47346-0001"))
    )
    (comp (ref "LED1")
      (value "LEDCHIPLED_1206")
      (footprint "eagle-import:CHIPLED_1206")
      (libsource (lib "eagle-import") (part "LEDCHIPLED_1206"))
    )
    (comp (ref "LED2")
      (value "LEDCHIPLED_1206")
      (footprint "eagle-import:CHIPLED_1206")
      (libsource (lib "eagle-import") (part "LEDCHIPLED_1206"))
    )
    (comp (ref "OC6")
      (value "TPTP08R")
      (footprint "eagle-import:TP08R")
      (libsource (lib "eagle-import") (part "TPTP08R"))
    )
    (comp (ref "R1")
      (value "10K")
      (footprint "eagle-import:R0805")
      (libsource (lib "eagle-import") (part "R-US_R0805"))
    )
    (comp (ref "R2")
      (value "470E")
      (footprint "eagle-import:R0805")
      (libsource (lib "eagle-import") (part "R-US_R0805"))
    )
    (comp (ref "R3")
      (value "10K")
      (footprint "eagle-import:R1206")
      (libsource (lib "eagle-import") (part "R-US_R1206"))
    )
    (comp (ref "R4")
      (value "10K")
      (footprint "eagle-import:R1206")
      (libsource (lib "eagle-import") (part "R-US_R1206"))
    )
    (comp (ref "R5")
      (value "330E")
      (footprint "eagle-import:R1206")
      (libsource (lib "eagle-import") (part "R-US_R1206"))
    )
    (comp (ref "R6")
      (value "10K")
      (footprint "eagle-import:R1206")
      (libsource (lib "eagle-import") (part "R-US_R1206"))
    )
    (comp (ref "R7")
      (value "330E")
      (footprint "eagle-import:R1206")
      (libsource (lib "eagle-import") (part "R-US_R1206"))
    )
    (comp (ref "RB12")
      (value "TPTP08R")
      (footprint "eagle-import:TP08R")
      (libsource (lib "eagle-import") (part "TPTP08R"))
    )
    (comp (ref "RB13")
      (value "TPTP08R")
      (footprint "eagle-import:TP08R")
      (libsource (lib "eagle-import") (part "TPTP08R"))
    )
    (comp (ref "RB14")
      (value "TPTP08R")
      (footprint "eagle-import:TP08R")
      (libsource (lib "eagle-import") (part "TPTP08R"))
    )
    (comp (ref "RB15")
      (value "TPTP08R")
      (footprint "eagle-import:TP08R")
      (libsource (lib "eagle-import") (part "TPTP08R"))
    )
    (comp (ref "RF0")
      (value "TPTP08R")
      (footprint "eagle-import:TP08R")
      (libsource (lib "eagle-import") (part "TPTP08R"))
    )
    (comp (ref "RG1")
      (value "TPTP08R")
      (footprint "eagle-import:TP08R")
      (libsource (lib "eagle-import") (part "TPTP08R"))
    )
    (comp (ref "RG13")
      (value "TPTP08R")
      (footprint "eagle-import:TP08R")
      (libsource (lib "eagle-import") (part "TPTP08R"))
    )
    (comp (ref "RG14")
      (value "TPTP08R")
      (footprint "eagle-import:TP08R")
      (libsource (lib "eagle-import") (part "TPTP08R"))
    )
    (comp (ref "RX")
      (value "TPTP20R")
      (footprint "eagle-import:TP20R")
      (libsource (lib "eagle-import") (part "TPTP20R"))
    )
    (comp (ref "RX2/SDA2")
      (value "TPTP08R")
      (footprint "eagle-import:TP08R")
      (libsource (lib "eagle-import") (part "TPTP08R"))
    )
    (comp (ref "S1")
      (value "SWITCH-MOMENTARY-2SMD")
      (footprint "eagle-import:TACTILE_SWITCH_SMD")
      (libsource (lib "eagle-import") (part "SWITCH-MOMENTARY-2SMD"))
    )
    (comp (ref "SCK")
      (value "TPTP10R")
      (footprint "eagle-import:TP10R")
      (libsource (lib "eagle-import") (part "TPTP10R"))
    )
    (comp (ref "SDI")
      (value "TPTP10R")
      (footprint "eagle-import:TP10R")
      (libsource (lib "eagle-import") (part "TPTP10R"))
    )
    (comp (ref "SDO")
      (value "TPTP10R")
      (footprint "eagle-import:TP10R")
      (libsource (lib "eagle-import") (part "TPTP10R"))
    )
    (comp (ref "TP1")
      (value "DNP")
      (footprint "eagle-import:TP-1.00MM")
      (libsource (lib "eagle-import") (part "TPTP-1.00MM"))
    )
    (comp (ref "TP2")
      (value "DNP")
      (footprint "eagle-import:TP-1.00MM")
      (libsource (lib "eagle-import") (part "TPTP-1.00MM"))
    )
    (comp (ref "TP3")
      (value "DNP")
      (footprint "eagle-import:TP-1.00MM")
      (libsource (lib "eagle-import") (part "TPTP-1.00MM"))
    )
    (comp (ref "TP4")
      (value "DNP")
      (footprint "eagle-import:TP-1.00MM")
      (libsource (lib "eagle-import") (part "TPTP-1.00MM"))
    )
    (comp (ref "TX")
      (value "TPTP20R")
      (footprint "eagle-import:TP20R")
      (libsource (lib "eagle-import") (part "TPTP20R"))
    )
    (comp (ref "TX2/SCL2")
      (value "TPTP08R")
      (footprint "eagle-import:TP08R")
      (libsource (lib "eagle-import") (part "TPTP08R"))
    )
  )
  (nets
    (net (code "1") (name "+3V3") (class "Default")
      (node (ref "3.3V") (pin "TP") (pinfunction "TP_TP") (pintype "input"))
      (node (ref "3V3") (pin "TP") (pinfunction "TP_TP") (pintype "input"))
      (node (ref "C19") (pin "1") (pinfunction "1_1") (pintype "passive"))
      (node (ref "C3") (pin "1") (pinfunction "1_1") (pintype "passive"))
      (node (ref "C4") (pin "1") (pinfunction "1_1") (pintype "passive"))
      (node (ref "C5") (pin "1") (pinfunction "1_1") (pintype "passive"))
      (node (ref "IC11") (pin "3") (pinfunction "VDD1_3") (pintype "bidirectional"))
      (node (ref "IC13") (pin "5") (pinfunction "OUT_5") (pintype "bidirectional"))
      (node (ref "IC15") (pin "10") (pinfunction "VDD_1_10") (pintype "bidirectional"))
      (node (ref "IC15") (pin "19") (pinfunction "AVDD_19") (pintype "bidirectional"))
      (node (ref "IC15") (pin "26") (pinfunction "VDD_2_26") (pintype "bidirectional"))
      (node (ref "IC15") (pin "38") (pinfunction "VDD_3_38") (pintype "bidirectional"))
      (node (ref "IC15") (pin "57") (pinfunction "VDD_4_57") (pintype "bidirectional"))
      (node (ref "J1") (pin "2") (pinfunction "S_2") (pintype "passive"))
      (node (ref "K2") (pin "1") (pinfunction "+_CONTROL_1") (pintype "bidirectional"))
      (node (ref "R1") (pin "2") (pinfunction "2_2") (pintype "passive"))
      (node (ref "R17") (pin "2") (pinfunction "2_2") (pintype "passive"))
      (node (ref "R3") (pin "1") (pinfunction "1_1") (pintype "passive"))
      (node (ref "R36") (pin "2") (pinfunction "2_2") (pintype "passive"))
      (node (ref "R37") (pin "2") (pinfunction "2_2") (pintype "passive"))
      (node (ref "R4") (pin "1") (pinfunction "1_1") (pintype "passive"))
      (node (ref "R8") (pin "1") (pinfunction "1_1") (pintype "passive"))
      (node (ref "RN1") (pin "2") (pinfunction "R1_2_2") (pintype "bidirectional"))
      (node (ref "RN2") (pin "6") (pinfunction "6_6") (pintype "bidirectional"))
      (node (ref "RN2") (pin "7") (pinfunction "7_7") (pintype "bidirectional"))
      (node (ref "S2") (pin "3") (pinfunction "A_3") (pintype "bidirectional"))
    )
    (net (code "2") (name "+5V") (class "Default")
      (node (ref "+5V") (pin "TP") (pinfunction "TP_TP") (pintype "input"))
      (node (ref "C12") (pin "1") (pinfunction "1_1") (pintype "passive"))
      (node (ref "C14") (pin "1") (pinfunction "1_1") (pintype "passive"))
      (node (ref "C15") (pin "1") (pinfunction "1_1") (pintype "passive"))
      (node (ref "C21") (pin "1") (pinfunction "1_1") (pintype "passive"))
      (node (ref "C7") (pin "1") (pinfunction "1_1") (pintype "passive"))
      (node (ref "C8") (pin "1") (pinfunction "1_1") (pintype "passive"))
      (node (ref "C9") (pin "1") (pinfunction "1_1") (pintype "passive"))
      (node (ref "IC11") (pin "10") (pinfunction "VDD2_10") (pintype "bidirectional"))
      (node (ref "IC12") (pin "4") (pinfunction "VDD_4") (pintype "bidirectional"))
      (node (ref "IC3") (pin "8") (pinfunction "VCC_8") (pintype "power_in"))
      (node (ref "IC4") (pin "8") (pinfunction "VCC_8") (pintype "power_in"))
      (node (ref "IC6") (pin "6") (pinfunction "VCC_6") (pintype "bidirectional"))
      (node (ref "IC9") (pin "14") (pinfunction "~{WP}_14") (pintype "bidirectional"))
      (node (ref "IC9") (pin "15") (pinfunction "~{RESET}_15") (pintype "bidirectional"))
      (node (ref "IC9") (pin "17") (pinfunction "VDD_17") (pintype "power_in"))
      (node (ref "PS3") (pin "4") (pinfunction "+VOUT_4") (pintype "bidirectional"))
      (node (ref "R9") (pin "1") (pinfunction "1_1") (pintype "passive"))
      (node (ref "RN1") (pin "4") (pinfunction "R2_2_4") (pintype "bidirectional"))
      (node (ref "RN1") (pin "6") (pinfunction "R3_2_6") (pintype "bidirectional"))
      (node (ref "RN1") (pin "8") (pinfunction "R4_2_8") (pintype "bidirectional"))
      (node (ref "RN2") (pin "5") (pinfunction "5_5") (pintype "bidirectional"))
      (node (ref "U9") (pin "1") (pinfunction "IN_1") (pintype "input"))
    )
    (net (code "3") (name "AGND") (class "Default")
      (node (ref "AGND") (pin "TP") (pinfunction "TP_TP") (pintype "input"))
      (node (ref "C11") (pin "2") (pinfunction "2_2") (pintype "passive"))
      (node (ref "C12") (pin "2") (pinfunction "2_2") (pintype "passive"))
      (node (ref "C14") (pin "2") (pinfunction "2_2") (pintype "passive"))
      (node (ref "C15") (pin "2") (pinfunction "2_2") (pintype "passive"))
      (node (ref "C16") (pin "2") (pinfunction "2_2") (pintype "passive"))
      (node (ref "C21") (pin "2") (pinfunction "2_2") (pintype "passive"))
      (node (ref "C31") (pin "1") (pinfunction "1_1") (pintype "passive"))
      (node (ref "C32") (pin "2") (pinfunction "2_2") (pintype "passive"))
      (node (ref "C35") (pin "2") (pinfunction "2_2") (pintype "passive"))
      (node (ref "C36") (pin "2") (pinfunction "2_2") (pintype "passive"))
      (node (ref "C37") (pin "2") (pinfunction "2_2") (pintype "passive"))
      (node (ref "C38") (pin "2") (pinfunction "2_2") (pintype "passive"))
      (node (ref "C7") (pin "2") (pinfunction "2_2") (pintype "passive"))
      (node (ref "C8") (pin "2") (pinfunction "2_2") (pintype "passive"))
      (node (ref "C9") (pin "2") (pinfunction "2_2") (pintype "passive"))
      (node (ref "IC11") (pin "14") (pinfunction "GND2_2_14") (pintype "bidirectional"))
      (node (ref "IC11") (pin "9") (pinfunction "GND2_1_9") (pintype "bidirectional"))
      (node (ref "IC12") (pin "11") (pinfunction "VSS_11") (pintype "bidirectional"))
      (node (ref "IC3") (pin "5") (pinfunction "GND_5") (pintype "power_in"))
      (node (ref "IC4") (pin "5") (pinfunction "GND_5") (pintype "power_in"))
      (node (ref "IC6") (pin "1") (pinfunction "IN-_1") (pintype "bidirectional"))
      (node (ref "IC6") (pin "2") (pinfunction "GND_2") (pintype "bidirectional"))
      (node (ref "IC6") (pin "4") (pinfunction "SHDN_4") (pintype "bidirectional"))
      (node (ref "IC9") (pin "13") (pinfunction "P0B_13") (pintype "bidirectional"))
      (node (ref "IC9") (pin "18") (pinfunction "P2B_18") (pintype "bidirectional"))
      (node (ref "IC9") (pin "3") (pinfunction "P3B_3") (pintype "bidirectional"))
      (node (ref "IC9") (pin "7") (pinfunction "VSS_7") (pintype "power_in"))
      (node (ref "IC9") (pin "8") (pinfunction "P1B_8") (pintype "bidirectional"))
      (node (ref "PS1") (pin "5") (pinfunction "-VOUT_5") (pintype "bidirectional"))
      (node (ref "PS2") (pin "5") (pinfunction "-VOUT_5") (pintype "bidirectional"))
      (node (ref "PS2") (pin "6") (pinfunction "0V_6") (pintype "bidirectional"))
      (node (ref "PS2") (pin "7") (pinfunction "+VOUT_7") (pintype "bidirectional"))
      (node (ref "PS3") (pin "3") (pinfunction "-VOUT_3") (pintype "bidirectional"))
      (node (ref "PS4") (pin "3") (pinfunction "-VOUT_3") (pintype "bidirectional"))
      (node (ref "PS5") (pin "3") (pinfunction "-VOUT_3") (pintype "bidirectional"))
      (node (ref "PS5") (pin "4") (pinfunction "+VOUT_4") (pintype "bidirectional"))
      (node (ref "PS5") (pin "5") (pinfunction "0V_5") (pintype "bidirectional"))
      (node (ref "PS6") (pin "4") (pinfunction "+VOUT_4") (pintype "bidirectional"))
      (node (ref "PS7") (pin "7") (pinfunction "+VOUT_7") (pintype "bidirectional"))
      (node (ref "R10") (pin "1") (pinfunction "1_1") (pintype "passive"))
      (node (ref "U9") (pin "3") (pinfunction "GND_3") (pintype "power_in"))
    )
    (net (code "4") (name "AREF") (class "Default")
      (node (ref "JP3") (pin "8") (pinfunction "8_8") (pintype "passive"))
    )
    (net (code "5") (name "BD+") (class "Default")
      (node (ref "IC2") (pin "15") (pinfunction "USBDP_15") (pintype "bidirectional"))
      (node (ref "J2") (pin "3") (pinfunction "D+_3") (pintype "bidirectional"))
      (node (ref "TP1") (pin "X") (pinfunction "P$1_X") (pintype "passive"))
    )
    (net (code "6") (name "BD-") (class "Default")
      (node (ref "IC2") (pin "16") (pinfunction "USBDM_16") (pintype "bidirectional"))
      (node (ref "J2") (pin "2") (pinfunction "D-_2") (pintype "bidirectional"))
      (node (ref "TP2") (pin "X") (pinfunction "P$1_X") (pintype "passive"))
    )
    (net (code "7") (name "CH1_EN~{}") (class "Default")
      (node (ref "IC15") (pin "15") (pinfunction "PGEC3/AN1/CMP1B/CN3/RB1_15") (pintype "bidirectional"))
      (node (ref "K1") (pin "2") (pinfunction "-_CONTROL_1_2") (pintype "bidirectional"))
    )
    (net (code "8") (name "CH2_EN~{}") (class "Default")
      (node (ref "IC15") (pin "14") (pinfunction "AN2/CMP1C/CMP2A/~{ASS1}/CN4/RB2_14") (pintype "bidirectional"))
      (node (ref "K1") (pin "4") (pinfunction "-_CONTROL_2_4") (pintype "bidirectional"))
    )
    (net (code "9") (name "COMM_RET") (class "Default")
      (node (ref "IC6") (pin "8") (pinfunction "IN+_8") (pintype "bidirectional"))
      (node (ref "J3") (pin "P$2") (pinfunction "2_P$2") (pintype "passive"))
      (node (ref "J3") (pin "P$3") (pinfunction "3_P$3") (pintype "passive"))
      (node (ref "J4") (pin "P$2") (pinfunction "2_P$2") (pintype "passive"))
      (node (ref "J4") (pin "P$3") (pinfunction "3_P$3") (pintype "passive"))
      (node (ref "R10") (pin "2") (pinfunction "2_2") (pintype "passive"))
      (node (ref "R16") (pin "2") (pinfunction "2_2") (pintype "passive"))
      (node (ref "R23") (pin "2") (pinfunction "2_2") (pintype "passive"))
    )
    (net (code "10") (name "CS_DIGIPOT") (class "Default")
      (node (ref "CS1") (pin "TP") (pinfunction "TP_TP") (pintype "input"))
      (node (ref "IC15") (pin "8") (pinfunction "~{SS2}/FLT9/SYNCI2/T5CK/CN11/RG9_8") (pintype "bidirectional"))
      (node (ref "RN2") (pin "8") (pinfunction "8_8") (pintype "bidirectional"))
    )
    (net (code "11") (name "CS_ISO") (class "Default")
      (node (ref "IC11") (pin "13") (pinfunction "V01_13") (pintype "bidirectional"))
      (node (ref "IC9") (pin "4") (pinfunction "~{CS}_4") (pintype "input"))
      (node (ref "RN1") (pin "3") (pinfunction "R2_1_3") (pintype "bidirectional"))
    )
    (net (code "12") (name "D9") (class "Default")
      (node (ref "IC15") (pin "43") (pinfunction "IC2/FLT2/~{U1CTS}/INT2/RD9_43") (pintype "bidirectional"))
      (node (ref "JP3") (pin "2") (pinfunction "2_2") (pintype "passive"))
      (node (ref "R26") (pin "2") (pinfunction "2_2") (pintype "passive"))
    )
    (net (code "13") (name "D10") (class "Default")
      (node (ref "IC15") (pin "44") (pinfunction "IC3/INDX1/FLT3/INT3/RD10_44") (pintype "bidirectional"))
      (node (ref "JP3") (pin "3") (pinfunction "3_3") (pintype "passive"))
      (node (ref "R27") (pin "2") (pinfunction "2_2") (pintype "passive"))
    )
    (net (code "14") (name "DC_5V") (class "Default")
      (node (ref "C27") (pin "1") (pinfunction "1_1") (pintype "passive"))
      (node (ref "IC14") (pin "4") (pinfunction "OUT_4") (pintype "bidirectional"))
      (node (ref "R32") (pin "1") (pinfunction "1_1") (pintype "passive"))
      (node (ref "U6") (pin "1") (pinfunction "VIN_1") (pintype "power_in"))
      (node (ref "U7") (pin "3") (pinfunction "D_3") (pintype "passive"))
    )
    (net (code "15") (name "EOFF_R~{}") (class "Default")
      (node (ref "IC15") (pin "18") (pinfunction "PGED1/AN7/CMP4B/RB7_18") (pintype "bidirectional"))
      (node (ref "Q8") (pin "1") (pinfunction "B_1") (pintype "bidirectional"))
    )
    (net (code "16") (name "ERR_FLG") (class "Default")
      (node (ref "IC14") (pin "3") (pinfunction "FLG_3") (pintype "bidirectional"))
      (node (ref "IC15") (pin "35") (pinfunction "~{U1RTS}/SCK1/INT0/RF6_35") (pintype "bidirectional"))
      (node (ref "R32") (pin "2") (pinfunction "2_2") (pintype "passive"))
    )
    (net (code "17") (name "GND") (class "Default")
      (node (ref "C1") (pin "2") (pinfunction "2_2") (pintype "passive"))
      (node (ref "C13") (pin "2") (pinfunction "2_2") (pintype "passive"))
      (node (ref "C16") (pin "1") (pinfunction "1_1") (pintype "passive"))
      (node (ref "C19") (pin "2") (pinfunction "2_2") (pintype "passive"))
      (node (ref "C2") (pin "2") (pinfunction "-_2") (pintype "bidirectional"))
      (node (ref "C25") (pin "2") (pinfunction "2_2") (pintype "passive"))
      (node (ref "C26") (pin "2") (pinfunction "2_2") (pintype "passive"))
      (node (ref "C27") (pin "2") (pinfunction "2_2") (pintype "passive"))
      (node (ref "C28") (pin "2") (pinfunction "2_2") (pintype "passive"))
      (node (ref "C29") (pin "-") (pinfunction "-_-") (pintype "passive"))
      (node (ref "C3") (pin "2") (pinfunction "2_2") (pintype "passive"))
      (node (ref "C4") (pin "2") (pinfunction "2_2") (pintype "passive"))
      (node (ref "C5") (pin "2") (pinfunction "2_2") (pintype "passive"))
      (node (ref "C6") (pin "2") (pinfunction "2_2") (pintype "passive"))
      (node (ref "DGND") (pin "TP") (pinfunction "TP_TP") (pintype "input"))
      (node (ref "GND") (pin "TP") (pinfunction "TP_TP") (pintype "input"))
      (node (ref "IC11") (pin "1") (pinfunction "GND1_CATHODE1_1") (pintype "bidirectional"))
      (node (ref "IC13") (pin "2") (pinfunction "GND_2") (pintype "bidirectional"))
      (node (ref "IC14") (pin "5") (pinfunction "GND_1_5") (pintype "bidirectional"))
      (node (ref "IC14") (pin "6") (pinfunction "GND_2_6") (pintype "bidirectional"))
      (node (ref "IC14") (pin "7") (pinfunction "GND_3_7") (pintype "bidirectional"))
      (node (ref "IC14") (pin "8") (pinfunction "GND_4_8") (pintype "bidirectional"))
      (node (ref "IC15") (pin "20") (pinfunction "AVSS_20") (pintype "bidirectional"))
      (node (ref "IC15") (pin "25") (pinfunction "VSS_2_25") (pintype "bidirectional"))
      (node (ref "IC15") (pin "41") (pinfunction "VSS_3_41") (pintype "bidirectional"))
      (node (ref "IC15") (pin "9") (pinfunction "VSS_1_9") (pintype "bidirectional"))
      (node (ref "IC2") (pin "18") (pinfunction "GND_18") (pintype "power_in"))
      (node (ref "IC2") (pin "21") (pinfunction "GND_21") (pintype "power_in"))
      (node (ref "IC2") (pin "25") (pinfunction "GND_25") (pintype "power_in"))
      (node (ref "IC2") (pin "26") (pinfunction "TEST_26") (pintype "input"))
      (node (ref "IC2") (pin "7") (pinfunction "GND_7") (pintype "power_in"))
      (node (ref "J1") (pin "3") (pinfunction "S_3") (pintype "passive"))
      (node (ref "J2") (pin "5") (pinfunction "GND_5") (pintype "bidirectional"))
      (node (ref "J7") (pin "2") (pinfunction "2_2") (pintype "bidirectional"))
      (node (ref "J7") (pin "3") (pinfunction "3_3") (pintype "bidirectional"))
      (node (ref "JP3") (pin "7") (pinfunction "7_7") (pintype "passive"))
      (node (ref "JP6") (pin "6") (pinfunction "6_6") (pintype "passive"))
      (node (ref "JP6") (pin "7") (pinfunction "7_7") (pintype "passive"))
      (node (ref "LED5") (pin "C") (pinfunction "C_C") (pintype "passive"))
      (node (ref "LED6") (pin "C") (pinfunction "C_C") (pintype "passive"))
      (node (ref "LED7") (pin "C") (pinfunction "C_C") (pintype "passive"))
      (node (ref "LED8") (pin "C") (pinfunction "C_C") (pintype "passive"))
      (node (ref "PS1") (pin "2") (pinfunction "-VIN_2") (pintype "bidirectional"))
      (node (ref "PS2") (pin "2") (pinfunction "-VIN_2") (pintype "bidirectional"))
      (node (ref "PS3") (pin "1") (pinfunction "-VIN_(GND)_1") (pintype "bidirectional"))
      (node (ref "PS4") (pin "1") (pinfunction "-VIN_1") (pintype "bidirectional"))
      (node (ref "PS5") (pin "1") (pinfunction "-VIN_1") (pintype "bidirectional"))
      (node (ref "PS6") (pin "1") (pinfunction "-VIN_1") (pintype "bidirectional"))
      (node (ref "PS7") (pin "2") (pinfunction "-VIN_2") (pintype "bidirectional"))
      (node (ref "Q8") (pin "3") (pinfunction "C_3") (pintype "bidirectional"))
      (node (ref "S1") (pin "1") (pinfunction "1_1") (pintype "passive"))
      (node (ref "S2") (pin "1") (pinfunction "COM_1") (pintype "bidirectional"))
      (node (ref "TP4") (pin "X") (pinfunction "P$1_X") (pintype "passive"))
      (node (ref "U6") (pin "2") (pinfunction "GND_2") (pintype "passive"))
      (node (ref "U6") (pin "3") (pinfunction "CTL_3") (pintype "input"))
    )
    (net (code "18") (name "INT0") (class "Default")
      (node (ref "IC15") (pin "42") (pinfunction "IC1/FLT1/SYNCI1/INT1/RD8_42") (pintype "bidirectional"))
      (node (ref "R17") (pin "1") (pinfunction "1_1") (pintype "passive"))
      (node (ref "S2") (pin "2") (pinfunction "NO_2") (pintype "bidirectional"))
    )
    (net (code "19") (name "IOUT") (class "Default")
      (node (ref "IC15") (pin "22") (pinfunction "AN9/DACOUT/RB9_22") (pintype "bidirectional"))
      (node (ref "JP2") (pin "1") (pinfunction "1_1") (pintype "passive"))
      (node (ref "R24") (pin "1") (pinfunction "1_1") (pintype "passive"))
    )
    (net (code "20") (name "MASTER-RESET") (class "Default")
      (node (ref "C1") (pin "1") (pinfunction "1_1") (pintype "passive"))
      (node (ref "JP6") (pin "3") (pinfunction "3_3") (pintype "passive"))
      (node (ref "R1") (pin "1") (pinfunction "1_1") (pintype "passive"))
      (node (ref "R2") (pin "1") (pinfunction "1_1") (pintype "passive"))
      (node (ref "S1") (pin "3") (pinfunction "2_3") (pintype "passive"))
    )
    (net (code "21") (name "Net-(C2-+)") (class "Default")
      (node (ref "C2") (pin "1") (pinfunction "+_1") (pintype "bidirectional"))
      (node (ref "IC15") (pin "56") (pinfunction "VCAP_56") (pintype "bidirectional"))
    )
    (net (code "22") (name "Net-(C11-Pad1)") (class "Default")
      (node (ref "C11") (pin "1") (pinfunction "1_1") (pintype "passive"))
      (node (ref "R24") (pin "2") (pinfunction "2_2") (pintype "passive"))
      (node (ref "R28") (pin "2") (pinfunction "2_2") (pintype "passive"))
    )
    (net (code "23") (name "Net-(D2-A)") (class "Default")
      (node (ref "D2") (pin "P$2") (pinfunction "A_P$2") (pintype "bidirectional"))
      (node (ref "D3") (pin "A") (pinfunction "A_A") (pintype "passive"))
      (node (ref "L1") (pin "1") (pinfunction "1_1") (pintype "passive"))
    )
    (net (code "24") (name "Net-(D5-A)") (class "Default")
      (node (ref "D5") (pin "2") (pinfunction "A_2") (pintype "bidirectional"))
      (node (ref "JP6") (pin "5") (pinfunction "5_5") (pintype "passive"))
    )
    (net (code "25") (name "Net-(D6-Pad2)") (class "Default")
      (node (ref "D6") (pin "2") (pinfunction "2_2") (pintype "passive"))
      (node (ref "R13") (pin "1") (pinfunction "1_1") (pintype "passive"))
    )
    (net (code "26") (name "Net-(D7-Pad1)") (class "Default")
      (node (ref "D7") (pin "1") (pinfunction "1_1") (pintype "passive"))
      (node (ref "R12") (pin "2") (pinfunction "2_2") (pintype "passive"))
    )
    (net (code "27") (name "Net-(D8-Pad2)") (class "Default")
      (node (ref "D8") (pin "2") (pinfunction "2_2") (pintype "passive"))
      (node (ref "R20") (pin "1") (pinfunction "1_1") (pintype "passive"))
    )
    (net (code "28") (name "Net-(D9-Pad1)") (class "Default")
      (node (ref "D9") (pin "1") (pinfunction "1_1") (pintype "passive"))
      (node (ref "R19") (pin "2") (pinfunction "2_2") (pintype "passive"))
    )
    (net (code "29") (name "Net-(IC2-3V3OUT)") (class "Default")
      (node (ref "IC2") (pin "17") (pinfunction "3V3OUT_17") (pintype "output"))
      (node (ref "IC2") (pin "4") (pinfunction "VCCIO_4") (pintype "power_in"))
    )
    (net (code "30") (name "Net-(IC2-CBUS0)") (class "Default")
      (node (ref "IC2") (pin "23") (pinfunction "CBUS0_23") (pintype "bidirectional"))
      (node (ref "LED2") (pin "C") (pinfunction "C_C") (pintype "passive"))
    )
    (net (code "31") (name "Net-(IC2-CBUS1)") (class "Default")
      (node (ref "IC2") (pin "22") (pinfunction "CBUS1_22") (pintype "bidirectional"))
      (node (ref "LED1") (pin "C") (pinfunction "C_C") (pintype "passive"))
    )
    (net (code "32") (name "Net-(IC2-CBUS3)") (class "Default")
      (node (ref "IC2") (pin "14") (pinfunction "CBUS3_14") (pintype "bidirectional"))
      (node (ref "R6") (pin "1") (pinfunction "1_1") (pintype "passive"))
    )
    (net (code "33") (name "Net-(IC3-V01)") (class "Default")
      (node (ref "IC3") (pin "7") (pinfunction "V01_7") (pintype "bidirectional"))
      (node (ref "IC9") (pin "20") (pinfunction "P2A_20") (pintype "bidirectional"))
      (node (ref "R9") (pin "2") (pinfunction "2_2") (pintype "passive"))
    )
    (net (code "34") (name "Net-(IC3-V02)") (class "Default")
      (node (ref "IC3") (pin "6") (pinfunction "V02_6") (pintype "bidirectional"))
      (node (ref "IC9") (pin "1") (pinfunction "P3A_1") (pintype "bidirectional"))
      (node (ref "R9") (pin "3") (pinfunction "3_3") (pintype "passive"))
    )
    (net (code "35") (name "Net-(IC3-VF1+)") (class "Default")
      (node (ref "IC3") (pin "1") (pinfunction "VF1+_1") (pintype "bidirectional"))
      (node (ref "R8") (pin "3") (pinfunction "3_3") (pintype "passive"))
    )
    (net (code "36") (name "Net-(IC3-VF2+)") (class "Default")
      (node (ref "IC3") (pin "4") (pinfunction "VF2+_4") (pintype "bidirectional"))
      (node (ref "R8") (pin "2") (pinfunction "2_2") (pintype "passive"))
    )
    (net (code "37") (name "Net-(IC4-V01)") (class "Default")
      (node (ref "IC4") (pin "7") (pinfunction "V01_7") (pintype "bidirectional"))
      (node (ref "IC9") (pin "11") (pinfunction "P0A_11") (pintype "bidirectional"))
      (node (ref "R9") (pin "4") (pinfunction "4_4") (pintype "passive"))
    )
    (net (code "38") (name "Net-(IC4-V02)") (class "Default")
      (node (ref "IC4") (pin "6") (pinfunction "V02_6") (pintype "bidirectional"))
      (node (ref "IC9") (pin "10") (pinfunction "P1A_10") (pintype "bidirectional"))
      (node (ref "R9") (pin "5") (pinfunction "5_5") (pintype "passive"))
    )
    (net (code "39") (name "Net-(IC4-VF1+)") (class "Default")
      (node (ref "IC4") (pin "1") (pinfunction "VF1+_1") (pintype "bidirectional"))
      (node (ref "R8") (pin "5") (pinfunction "5_5") (pintype "passive"))
    )
    (net (code "40") (name "Net-(IC4-VF2+)") (class "Default")
      (node (ref "IC4") (pin "4") (pinfunction "VF2+_4") (pintype "bidirectional"))
      (node (ref "R8") (pin "4") (pinfunction "4_4") (pintype "passive"))
    )
    (net (code "41") (name "Net-(IC5-REF_A)") (class "Default")
      (node (ref "IC5") (pin "1") (pinfunction "REF_B_1") (pintype "input"))
      (node (ref "IC5") (pin "5") (pinfunction "REF_A_5") (pintype "input"))
      (node (ref "IC7") (pin "2") (pinfunction "-IN_2") (pintype "input"))
      (node (ref "IC7") (pin "6") (pinfunction "OUT_6") (pintype "output"))
      (node (ref "VF/B1") (pin "TP") (pinfunction "TP_TP") (pintype "input"))
    )
    (net (code "42") (name "Net-(IC5-V+)") (class "Default")
      (node (ref "IC5") (pin "7") (pinfunction "V+_7") (pintype "power_in"))
      (node (ref "IC7") (pin "7") (pinfunction "V+_7") (pintype "bidirectional"))
      (node (ref "Q2") (pin "1") (pinfunction "E_1") (pintype "bidirectional"))
      (node (ref "V1") (pin "TP") (pinfunction "TP_TP") (pintype "input"))
    )
    (net (code "43") (name "Net-(IC5-V-)") (class "Default")
      (node (ref "IC5") (pin "4") (pinfunction "V-_4") (pintype "power_in"))
      (node (ref "IC7") (pin "4") (pinfunction "V-_4") (pintype "bidirectional"))
      (node (ref "Q1") (pin "1") (pinfunction "E_1") (pintype "bidirectional"))
      (node (ref "V2") (pin "TP") (pinfunction "TP_TP") (pintype "input"))
    )
    (net (code "44") (name "Net-(IC5-V_OUT)") (class "Default")
      (node (ref "D6") (pin "1") (pinfunction "1_1") (pintype "passive"))
      (node (ref "D7") (pin "2") (pinfunction "2_2") (pintype "passive"))
      (node (ref "IC5") (pin "6") (pinfunction "V_OUT_6") (pintype "output"))
      (node (ref "R15") (pin "2") (pinfunction "2_2") (pintype "passive"))
    )
    (net (code "45") (name "Net-(IC6-OUT)") (class "Default")
      (node (ref "IC6") (pin "5") (pinfunction "OUT_5") (pintype "bidirectional"))
      (node (ref "R28") (pin "1") (pinfunction "1_1") (pintype "passive"))
    )
    (net (code "46") (name "Net-(IC6-VREF1)") (class "Default")
      (node (ref "1.6V") (pin "TP") (pinfunction "TP_TP") (pintype "input"))
      (node (ref "IC6") (pin "3") (pinfunction "VREF2_3") (pintype "bidirectional"))
      (node (ref "IC6") (pin "7") (pinfunction "VREF1_7") (pintype "bidirectional"))
      (node (ref "U9") (pin "2") (pinfunction "OUT_2") (pintype "output"))
    )
    (net (code "47") (name "Net-(IC7-+IN)") (class "Default")
      (node (ref "F2") (pin "1") (pinfunction "1_1") (pintype "bidirectional"))
      (node (ref "IC7") (pin "3") (pinfunction "+IN_3") (pintype "input"))
      (node (ref "K1") (pin "8") (pinfunction "LOAD_4_8") (pintype "bidirectional"))
      (node (ref "R15") (pin "1") (pinfunction "1_1") (pintype "passive"))
    )
    (net (code "48") (name "Net-(IC8-V_OUT)") (class "Default")
      (node (ref "D8") (pin "1") (pinfunction "1_1") (pintype "passive"))
      (node (ref "D9") (pin "2") (pinfunction "2_2") (pintype "passive"))
      (node (ref "IC8") (pin "6") (pinfunction "V_OUT_6") (pintype "output"))
      (node (ref "R22") (pin "2") (pinfunction "2_2") (pintype "passive"))
    )
    (net (code "49") (name "Net-(IC10-+IN)") (class "Default")
      (node (ref "F3") (pin "1") (pinfunction "1_1") (pintype "bidirectional"))
      (node (ref "IC10") (pin "3") (pinfunction "+IN_3") (pintype "input"))
      (node (ref "K1") (pin "6") (pinfunction "LOAD_2_6") (pintype "bidirectional"))
      (node (ref "R22") (pin "1") (pinfunction "1_1") (pintype "passive"))
    )
    (net (code "50") (name "Net-(IC10--IN)") (class "Default")
      (node (ref "IC10") (pin "2") (pinfunction "-IN_2") (pintype "input"))
      (node (ref "IC10") (pin "6") (pinfunction "OUT_6") (pintype "output"))
      (node (ref "IC8") (pin "1") (pinfunction "REF_B_1") (pintype "input"))
      (node (ref "IC8") (pin "5") (pinfunction "REF_A_5") (pintype "input"))
      (node (ref "VF/B2") (pin "TP") (pinfunction "TP_TP") (pintype "input"))
    )
    (net (code "51") (name "Net-(IC10-V+)") (class "Default")
      (node (ref "IC10") (pin "7") (pinfunction "V+_7") (pintype "bidirectional"))
      (node (ref "IC8") (pin "7") (pinfunction "V+_7") (pintype "power_in"))
      (node (ref "Q4") (pin "1") (pinfunction "E_1") (pintype "bidirectional"))
      (node (ref "V3") (pin "TP") (pinfunction "TP_TP") (pintype "input"))
    )
    (net (code "52") (name "Net-(IC10-V-)") (class "Default")
      (node (ref "IC10") (pin "4") (pinfunction "V-_4") (pintype "bidirectional"))
      (node (ref "IC8") (pin "4") (pinfunction "V-_4") (pintype "power_in"))
      (node (ref "Q3") (pin "1") (pinfunction "E_1") (pintype "bidirectional"))
      (node (ref "V4") (pin "TP") (pinfunction "TP_TP") (pintype "input"))
    )
    (net (code "53") (name "Net-(IC11-ANODE1)") (class "Default")
      (node (ref "IC11") (pin "4") (pinfunction "ANODE1_4") (pintype "bidirectional"))
      (node (ref "RN2") (pin "1") (pinfunction "1_1") (pintype "bidirectional"))
    )
    (net (code "54") (name "Net-(IC11-ANODE2)") (class "Default")
      (node (ref "IC11") (pin "6") (pinfunction "ANODE2_6") (pintype "bidirectional"))
      (node (ref "RN2") (pin "2") (pinfunction "2_2") (pintype "bidirectional"))
    )
    (net (code "55") (name "Net-(IC11-ANODE3)") (class "Default")
      (node (ref "IC11") (pin "8") (pinfunction "ANODE3_8") (pintype "bidirectional"))
      (node (ref "RN2") (pin "3") (pinfunction "3_3") (pintype "bidirectional"))
    )
    (net (code "56") (name "Net-(IC11-ANODE4)") (class "Default")
      (node (ref "IC11") (pin "15") (pinfunction "ANODE4_15") (pintype "bidirectional"))
      (node (ref "RN2") (pin "4") (pinfunction "4_4") (pintype "bidirectional"))
    )
    (net (code "57") (name "Net-(IC13-NR{slash}FB)") (class "Default")
      (node (ref "C28") (pin "1") (pinfunction "1_1") (pintype "passive"))
      (node (ref "IC13") (pin "4") (pinfunction "NR/FB_4") (pintype "bidirectional"))
    )
    (net (code "58") (name "Net-(IC15-AN14{slash}CMP3D{slash}~{SS1}{slash}~{U2RTS}{slash}RB14)") (class "Default")
      (node (ref "IC15") (pin "29") (pinfunction "AN14/CMP3D/~{SS1}/~{U2RTS}/RB14_29") (pintype "bidirectional"))
      (node (ref "RB14") (pin "TP") (pinfunction "TP_TP") (pintype "input"))
    )
    (net (code "59") (name "Net-(IC15-AN15{slash}CMP4D{slash}CN12{slash}RB15)") (class "Default")
      (node (ref "IC15") (pin "30") (pinfunction "AN15/CMP4D/CN12/RB15_30") (pintype "bidirectional"))
      (node (ref "RB15") (pin "TP") (pinfunction "TP_TP") (pintype "input"))
    )
    (net (code "60") (name "Net-(IC15-C1RX{slash}SYNCI4{slash}RF0)") (class "Default")
      (node (ref "IC15") (pin "58") (pinfunction "C1RX/SYNCI4/RF0_58") (pintype "bidirectional"))
      (node (ref "RF0") (pin "TP") (pinfunction "TP_TP") (pintype "input"))
    )
    (net (code "61") (name "Net-(IC15-PWM1L{slash}FLT8{slash}RE0)") (class "Default")
      (node (ref "IC15") (pin "60") (pinfunction "PWM1L/FLT8/RE0_60") (pintype "bidirectional"))
      (node (ref "RG1") (pin "TP") (pinfunction "TP_TP") (pintype "input"))
    )
    (net (code "62") (name "Net-(IC15-PWM2L{slash}RE2)") (class "Default")
      (node (ref "IC15") (pin "62") (pinfunction "PWM2L/RE2_62") (pintype "bidirectional"))
      (node (ref "RG14") (pin "TP") (pinfunction "TP_TP") (pintype "input"))
    )
    (net (code "63") (name "Net-(IC15-PWM3L{slash}RE4)") (class "Default")
      (node (ref "IC15") (pin "64") (pinfunction "PWM3L/RE4_64") (pintype "bidirectional"))
      (node (ref "RG13") (pin "TP") (pinfunction "TP_TP") (pintype "input"))
    )
    (net (code "64") (name "Net-(IC15-TCK{slash}AN12{slash}CMP1D{slash}RB12)") (class "Default")
      (node (ref "IC15") (pin "27") (pinfunction "TCK/AN12/CMP1D/RB12_27") (pintype "bidirectional"))
      (node (ref "RB12") (pin "TP") (pinfunction "TP_TP") (pintype "input"))
    )
    (net (code "65") (name "Net-(IC15-TDI{slash}AN13{slash}CMP2D{slash}RB13)") (class "Default")
      (node (ref "IC15") (pin "28") (pinfunction "TDI/AN13/CMP2D/RB13_28") (pintype "bidirectional"))
      (node (ref "RB13") (pin "TP") (pinfunction "TP_TP") (pintype "input"))
    )
    (net (code "66") (name "Net-(IC15-U2RX{slash}SDA2{slash}QEA2{slash}FLT17{slash}CN17{slash}RF4)") (class "Default")
      (node (ref "IC15") (pin "31") (pinfunction "U2RX/SDA2/QEA2/FLT17/CN17/RF4_31") (pintype "bidirectional"))
      (node (ref "RX2/SDA2") (pin "TP") (pinfunction "TP_TP") (pintype "input"))
    )
    (net (code "67") (name "Net-(IC15-U2TX{slash}SCL2{slash}QEB2{slash}FLT18{slash}CN18{slash}RF5)") (class "Default")
      (node (ref "IC15") (pin "32") (pinfunction "U2TX/SCL2/QEB2/FLT18/CN18/RF5_32") (pintype "bidirectional"))
      (node (ref "TX2/SCL2") (pin "TP") (pinfunction "TP_TP") (pintype "input"))
    )
    (net (code "68") (name "Net-(J3-1)") (class "Default")
      (node (ref "F2") (pin "2") (pinfunction "2_2") (pintype "bidirectional"))
      (node (ref "J3") (pin "P$1") (pinfunction "1_P$1") (pintype "passive"))
    )
    (net (code "69") (name "Net-(J4-1)") (class "Default")
      (node (ref "F3") (pin "2") (pinfunction "2_2") (pintype "bidirectional"))
      (node (ref "J4") (pin "P$1") (pinfunction "1_P$1") (pintype "passive"))
    )
    (net (code "70") (name "Net-(K1-+_CONTROL_1)") (class "Default")
      (node (ref "K1") (pin "1") (pinfunction "+_CONTROL_1_1") (pintype "bidirectional"))
      (node (ref "R37") (pin "1") (pinfunction "1_1") (pintype "passive"))
    )
    (net (code "71") (name "Net-(K1-+_CONTROL_2)") (class "Default")
      (node (ref "K1") (pin "3") (pinfunction "+_CONTROL_2_3") (pintype "bidirectional"))
      (node (ref "R36") (pin "1") (pinfunction "1_1") (pintype "passive"))
    )
    (net (code "72") (name "Net-(K1-LOAD_1)") (class "Default")
      (node (ref "K1") (pin "5") (pinfunction "LOAD_1_5") (pintype "bidirectional"))
      (node (ref "R23") (pin "1") (pinfunction "1_1") (pintype "passive"))
    )
    (net (code "73") (name "Net-(K1-LOAD_3)") (class "Default")
      (node (ref "K1") (pin "7") (pinfunction "LOAD_3_7") (pintype "bidirectional"))
      (node (ref "R16") (pin "1") (pinfunction "1_1") (pintype "passive"))
    )
    (net (code "74") (name "Net-(K2--_CONTROL)") (class "Default")
      (node (ref "K2") (pin "2") (pinfunction "-_CONTROL_2") (pintype "bidirectional"))
      (node (ref "R31") (pin "2") (pinfunction "2_2") (pintype "passive"))
    )
    (net (code "75") (name "Net-(K2-LOAD-)") (class "Default")
      (node (ref "K2") (pin "5") (pinfunction "LOAD-_5") (pintype "bidirectional"))
      (node (ref "PS1") (pin "1") (pinfunction "+VIN_1") (pintype "bidirectional"))
      (node (ref "PS2") (pin "1") (pinfunction "+VIN_1") (pintype "bidirectional"))
      (node (ref "PS4") (pin "2") (pinfunction "+VIN_2") (pintype "bidirectional"))
      (node (ref "PS5") (pin "2") (pinfunction "+VIN_2") (pintype "bidirectional"))
      (node (ref "PS6") (pin "2") (pinfunction "+VIN_2") (pintype "bidirectional"))
      (node (ref "PS7") (pin "1") (pinfunction "+VIN_1") (pintype "bidirectional"))
    )
    (net (code "76") (name "Net-(LED1-PadA)") (class "Default")
      (node (ref "LED1") (pin "A") (pinfunction "A_A") (pintype "passive"))
      (node (ref "R7") (pin "1") (pinfunction "1_1") (pintype "passive"))
    )
    (net (code "77") (name "Net-(LED2-PadA)") (class "Default")
      (node (ref "LED2") (pin "A") (pinfunction "A_A") (pintype "passive"))
      (node (ref "R5") (pin "1") (pinfunction "1_1") (pintype "passive"))
    )
    (net (code "78") (name "Net-(LED5-PadA)") (class "Default")
      (node (ref "LED5") (pin "A") (pinfunction "A_A") (pintype "passive"))
      (node (ref "R26") (pin "1") (pinfunction "1_1") (pintype "passive"))
    )
    (net (code "79") (name "Net-(LED6-PadA)") (class "Default")
      (node (ref "LED6") (pin "A") (pinfunction "A_A") (pintype "passive"))
      (node (ref "R27") (pin "1") (pinfunction "1_1") (pintype "passive"))
    )
    (net (code "80") (name "Net-(LED7-PadA)") (class "Default")
      (node (ref "LED7") (pin "A") (pinfunction "A_A") (pintype "passive"))
      (node (ref "R29") (pin "1") (pinfunction "1_1") (pintype "passive"))
    )
    (net (code "81") (name "Net-(LED8-PadA)") (class "Default")
      (node (ref "LED8") (pin "A") (pinfunction "A_A") (pintype "passive"))
      (node (ref "R30") (pin "1") (pinfunction "1_1") (pintype "passive"))
    )
    (net (code "82") (name "Net-(Q1-B)") (class "Default")
      (node (ref "C39") (pin "2") (pinfunction "2_2") (pintype "passive"))
      (node (ref "Q1") (pin "3") (pinfunction "B_3") (pintype "bidirectional"))
      (node (ref "R11") (pin "2") (pinfunction "2_2") (pintype "passive"))
      (node (ref "R12") (pin "1") (pinfunction "1_1") (pintype "passive"))
    )
    (net (code "83") (name "Net-(Q2-B)") (class "Default")
      (node (ref "C39") (pin "1") (pinfunction "1_1") (pintype "passive"))
      (node (ref "Q2") (pin "3") (pinfunction "B_3") (pintype "bidirectional"))
      (node (ref "R13") (pin "2") (pinfunction "2_2") (pintype "passive"))
      (node (ref "R14") (pin "1") (pinfunction "1_1") (pintype "passive"))
    )
    (net (code "84") (name "Net-(Q3-B)") (class "Default")
      (node (ref "C40") (pin "2") (pinfunction "2_2") (pintype "passive"))
      (node (ref "Q3") (pin "3") (pinfunction "B_3") (pintype "bidirectional"))
      (node (ref "R18") (pin "2") (pinfunction "2_2") (pintype "passive"))
      (node (ref "R19") (pin "1") (pinfunction "1_1") (pintype "passive"))
    )
    (net (code "85") (name "Net-(Q4-B)") (class "Default")
      (node (ref "C40") (pin "1") (pinfunction "1_1") (pintype "passive"))
      (node (ref "Q4") (pin "3") (pinfunction "B_3") (pintype "bidirectional"))
      (node (ref "R20") (pin "2") (pinfunction "2_2") (pintype "passive"))
      (node (ref "R21") (pin "1") (pinfunction "1_1") (pintype "passive"))
    )
    (net (code "86") (name "Net-(Q8-E)") (class "Default")
      (node (ref "Q8") (pin "2") (pinfunction "E_2") (pintype "bidirectional"))
      (node (ref "R34") (pin "1") (pinfunction "1_1") (pintype "passive"))
    )
    (net (code "87") (name "Net-(S2-K)") (class "Default")
      (node (ref "R34") (pin "2") (pinfunction "2_2") (pintype "passive"))
      (node (ref "S2") (pin "4") (pinfunction "K_4") (pintype "bidirectional"))
    )
    (net (code "88") (name "Net-(U6-GATE)") (class "Default")
      (node (ref "U6") (pin "5") (pinfunction "GATE_5") (pintype "passive"))
      (node (ref "U7") (pin "1") (pinfunction "G_1") (pintype "passive"))
    )
    (net (code "89") (name "OC1") (class "Default")
      (node (ref "IC15") (pin "46") (pinfunction "OC1/QEB1/FLT5/RD0_46") (pintype "bidirectional"))
      (node (ref "IC4") (pin "2") (pinfunction "VF1-_2") (pintype "bidirectional"))
      (node (ref "OC1") (pin "TP") (pinfunction "TP_TP") (pintype "input"))
    )
    (net (code "90") (name "OC1S") (class "Default")
      (node (ref "IC12") (pin "3") (pinfunction "VINA+_3") (pintype "bidirectional"))
      (node (ref "IC9") (pin "12") (pinfunction "P0W_12") (pintype "bidirectional"))
    )
    (net (code "91") (name "OC2") (class "Default")
      (node (ref "IC15") (pin "49") (pinfunction "OC2/SYNCO2/FLT6/RD1_49") (pintype "bidirectional"))
      (node (ref "IC4") (pin "3") (pinfunction "VF2-_3") (pintype "bidirectional"))
      (node (ref "OC2") (pin "TP") (pinfunction "TP_TP") (pintype "input"))
    )
    (net (code "92") (name "OC2S") (class "Default")
      (node (ref "IC12") (pin "5") (pinfunction "VINB+_5") (pintype "bidirectional"))
      (node (ref "IC9") (pin "9") (pinfunction "P1W_9") (pintype "bidirectional"))
    )
    (net (code "93") (name "OC3") (class "Default")
      (node (ref "IC15") (pin "50") (pinfunction "OC3/FLT7/RD2_50") (pintype "bidirectional"))
      (node (ref "IC3") (pin "2") (pinfunction "VF1-_2") (pintype "bidirectional"))
      (node (ref "OC3") (pin "TP") (pinfunction "TP_TP") (pintype "input"))
    )
    (net (code "94") (name "OC3S") (class "Default")
      (node (ref "IC12") (pin "10") (pinfunction "VINC+_10") (pintype "bidirectional"))
      (node (ref "IC9") (pin "19") (pinfunction "P2W_19") (pintype "bidirectional"))
    )
    (net (code "95") (name "OC4") (class "Default")
      (node (ref "IC15") (pin "51") (pinfunction "OC4/SYNCO1/RD3_51") (pintype "bidirectional"))
      (node (ref "IC3") (pin "3") (pinfunction "VF2-_3") (pintype "bidirectional"))
      (node (ref "OC4") (pin "TP") (pinfunction "TP_TP") (pintype "input"))
    )
    (net (code "96") (name "OC4S") (class "Default")
      (node (ref "IC12") (pin "12") (pinfunction "VIND+_12") (pintype "bidirectional"))
      (node (ref "IC9") (pin "2") (pinfunction "P3W_2") (pintype "bidirectional"))
    )
    (net (code "97") (name "OC5") (class "Default")
      (node (ref "/OC5") (pin "TP") (pinfunction "TP_TP") (pintype "input"))
      (node (ref "IC15") (pin "52") (pinfunction "PWM6L/CN13/RD4_52") (pintype "bidirectional"))
    )
    (net (code "98") (name "OC6") (class "Default")
      (node (ref "IC15") (pin "53") (pinfunction "PWM6H/CN14/RD5_53") (pintype "bidirectional"))
      (node (ref "OC6") (pin "TP") (pinfunction "TP_TP") (pintype "input"))
    )
    (net (code "99") (name "PGC_2") (class "Default")
      (node (ref "IC15") (pin "48") (pinfunction "PGEC2/SOSCO/T1CK/CN0/RC14_48") (pintype "bidirectional"))
      (node (ref "J1") (pin "5") (pinfunction "S_5") (pintype "passive"))
    )
    (net (code "100") (name "PGD_2") (class "Default")
      (node (ref "IC15") (pin "47") (pinfunction "PGED2/SOSCI/T4CK/CN1/RC13_47") (pintype "bidirectional"))
      (node (ref "J1") (pin "4") (pinfunction "S_4") (pintype "passive"))
    )
    (net (code "101") (name "PWM2") (class "Default")
      (node (ref "JP4") (pin "3") (pinfunction "3_3") (pintype "passive"))
    )
    (net (code "102") (name "PWM3") (class "Default")
      (node (ref "JP4") (pin "4") (pinfunction "4_4") (pintype "passive"))
    )
    (net (code "103") (name "PWM5") (class "Default")
      (node (ref "JP4") (pin "6") (pinfunction "6_6") (pintype "passive"))
    )
    (net (code "104") (name "PWM6") (class "Default")
      (node (ref "JP4") (pin "7") (pinfunction "7_7") (pintype "passive"))
    )
    (net (code "105") (name "PWM7") (class "Default")
      (node (ref "JP4") (pin "8") (pinfunction "8_8") (pintype "passive"))
    )
    (net (code "106") (name "PWM8") (class "Default")
      (node (ref "JP3") (pin "1") (pinfunction "1_1") (pintype "passive"))
    )
    (net (code "107") (name "PWM11") (class "Default")
      (node (ref "JP3") (pin "4") (pinfunction "4_4") (pintype "passive"))
    )
    (net (code "108") (name "PWM12") (class "Default")
      (node (ref "JP3") (pin "5") (pinfunction "5_5") (pintype "passive"))
    )
    (net (code "109") (name "PWM13") (class "Default")
      (node (ref "JP3") (pin "6") (pinfunction "6_6") (pintype "passive"))
    )
    (net (code "110") (name "RESET~{}") (class "Default")
      (node (ref "IC15") (pin "7") (pinfunction "~{MCLR}_7") (pintype "bidirectional"))
      (node (ref "J1") (pin "1") (pinfunction "S_1") (pintype "passive"))
      (node (ref "R2") (pin "2") (pinfunction "2_2") (pintype "passive"))
    )
    (net (code "111") (name "RX") (class "Default")
      (node (ref "JP4") (pin "1") (pinfunction "1_1") (pintype "passive"))
    )
    (net (code "112") (name "RXD0") (class "Default")
      (node (ref "JP5") (pin "2") (pinfunction "2_2") (pintype "passive"))
    )
    (net (code "113") (name "RXD1") (class "Default")
      (node (ref "JP5") (pin "4") (pinfunction "4_4") (pintype "passive"))
    )
    (net (code "114") (name "RXD2") (class "Default")
      (node (ref "JP5") (pin "6") (pinfunction "6_6") (pintype "passive"))
    )
    (net (code "115") (name "RX_1") (class "Default")
      (node (ref "IC15") (pin "34") (pinfunction "U1RX/SDI1/RF2_34") (pintype "bidirectional"))
      (node (ref "IC2") (pin "1") (pinfunction "TXD_1") (pintype "output"))
      (node (ref "RX") (pin "TP") (pinfunction "TP_TP") (pintype "input"))
    )
    (net (code "116") (name "SCK2") (class "Default")
      (node (ref "IC11") (pin "5") (pinfunction "CATHODE2_5") (pintype "bidirectional"))
      (node (ref "IC15") (pin "4") (pinfunction "SCK2/FLT12/CN8/RG6_4") (pintype "bidirectional"))
      (node (ref "SCK") (pin "TP") (pinfunction "TP_TP") (pintype "input"))
    )
    (net (code "117") (name "SCK_ISO") (class "Default")
      (node (ref "IC11") (pin "12") (pinfunction "V02_12") (pintype "bidirectional"))
      (node (ref "IC9") (pin "5") (pinfunction "SCK_5") (pintype "bidirectional"))
      (node (ref "RN1") (pin "5") (pinfunction "R3_1_5") (pintype "bidirectional"))
    )
    (net (code "118") (name "SCL0-3") (class "Default")
      (node (ref "JP5") (pin "8") (pinfunction "8_8") (pintype "passive"))
    )
    (net (code "119") (name "SCL1") (class "Default")
      (node (ref "IC15") (pin "37") (pinfunction "SCL1/RG2_37") (pintype "bidirectional"))
      (node (ref "JP3") (pin "10") (pinfunction "10_10") (pintype "passive"))
      (node (ref "R4") (pin "2") (pinfunction "2_2") (pintype "passive"))
    )
    (net (code "120") (name "SDA0-3") (class "Default")
      (node (ref "JP5") (pin "7") (pinfunction "7_7") (pintype "passive"))
    )
    (net (code "121") (name "SDA1") (class "Default")
      (node (ref "IC15") (pin "36") (pinfunction "SDA1/RG3_36") (pintype "bidirectional"))
      (node (ref "JP3") (pin "9") (pinfunction "9_9") (pintype "passive"))
      (node (ref "R3") (pin "2") (pinfunction "2_2") (pintype "passive"))
    )
    (net (code "122") (name "SDI2") (class "Default")
      (node (ref "IC11") (pin "2") (pinfunction "V04_2") (pintype "bidirectional"))
      (node (ref "IC15") (pin "5") (pinfunction "SDI2/FLT11/CN9/RG7_5") (pintype "bidirectional"))
      (node (ref "RN1") (pin "1") (pinfunction "R1_1_1") (pintype "bidirectional"))
      (node (ref "SDI") (pin "TP") (pinfunction "TP_TP") (pintype "input"))
    )
    (net (code "123") (name "SDI_ISO") (class "Default")
      (node (ref "IC11") (pin "16") (pinfunction "CATHODE4_16") (pintype "bidirectional"))
      (node (ref "IC9") (pin "16") (pinfunction "SDO_16") (pintype "bidirectional"))
    )
    (net (code "124") (name "SDO2") (class "Default")
      (node (ref "IC11") (pin "7") (pinfunction "CATHODE3_7") (pintype "bidirectional"))
      (node (ref "IC15") (pin "6") (pinfunction "SDO2/FLT10/CN10/RG8_6") (pintype "bidirectional"))
      (node (ref "SDO") (pin "TP") (pinfunction "TP_TP") (pintype "input"))
    )
    (net (code "125") (name "SDO_ISO") (class "Default")
      (node (ref "IC11") (pin "11") (pinfunction "V03_11") (pintype "bidirectional"))
      (node (ref "IC9") (pin "6") (pinfunction "SDI_6") (pintype "bidirectional"))
      (node (ref "RN1") (pin "7") (pinfunction "R4_1_7") (pintype "bidirectional"))
    )
    (net (code "126") (name "SS1{slash}PWM4") (class "Default")
      (node (ref "JP4") (pin "5") (pinfunction "5_5") (pintype "passive"))
    )
    (net (code "127") (name "STIM1_LED") (class "Default")
      (node (ref "IC15") (pin "16") (pinfunction "PGED3/AN0/CMP1A/CMP4C/CN2/RB0_16") (pintype "bidirectional"))
      (node (ref "R29") (pin "2") (pinfunction "2_2") (pintype "passive"))
    )
    (net (code "128") (name "STIM2_LED") (class "Default")
      (node (ref "IC15") (pin "17") (pinfunction "PGEC1/AN6/CMP3C/CMP4A/OCFA/RB6_17") (pintype "bidirectional"))
      (node (ref "R30") (pin "2") (pinfunction "2_2") (pintype "passive"))
    )
    (net (code "129") (name "SUPPLY_STATUS") (class "Default")
      (node (ref "IC15") (pin "40") (pinfunction "OSC2/REFCLKO/CLKO/RC15_40") (pintype "bidirectional"))
      (node (ref "R33") (pin "2") (pinfunction "2_2") (pintype "passive"))
      (node (ref "U6") (pin "4") (pinfunction "STAT_4") (pintype "output"))
    )
    (net (code "130") (name "TX") (class "Default")
      (node (ref "JP4") (pin "2") (pinfunction "2_2") (pintype "passive"))
    )
    (net (code "131") (name "TXD0") (class "Default")
      (node (ref "JP5") (pin "1") (pinfunction "1_1") (pintype "passive"))
    )
    (net (code "132") (name "TXD1") (class "Default")
      (node (ref "JP5") (pin "3") (pinfunction "3_3") (pintype "passive"))
    )
    (net (code "133") (name "TXD2") (class "Default")
      (node (ref "JP5") (pin "5") (pinfunction "5_5") (pintype "passive"))
    )
    (net (code "134") (name "TX_1") (class "Default")
      (node (ref "IC15") (pin "33") (pinfunction "U1TX/SDO1/RF3_33") (pintype "bidirectional"))
      (node (ref "IC2") (pin "5") (pinfunction "RXD_5") (pintype "input"))
      (node (ref "TX") (pin "TP") (pinfunction "TP_TP") (pintype "input"))
    )
    (net (code "135") (name "USB_5V") (class "Default")
      (node (ref "C6") (pin "1") (pinfunction "1_1") (pintype "passive"))
      (node (ref "D4") (pin "2") (pinfunction "A_2") (pintype "bidirectional"))
      (node (ref "F1") (pin "1") (pinfunction "1_1") (pintype "passive"))
      (node (ref "IC2") (pin "20") (pinfunction "VCC_20") (pintype "power_in"))
      (node (ref "R5") (pin "2") (pinfunction "2_2") (pintype "passive"))
      (node (ref "R6") (pin "2") (pinfunction "2_2") (pintype "passive"))
      (node (ref "R7") (pin "2") (pinfunction "2_2") (pintype "passive"))
    )
    (net (code "136") (name "VCC") (class "Default")
      (node (ref "+HV") (pin "TP") (pinfunction "TP_TP") (pintype "input"))
      (node (ref "C32") (pin "1") (pinfunction "1_1") (pintype "passive"))
      (node (ref "C35") (pin "1") (pinfunction "1_1") (pintype "passive"))
      (node (ref "C37") (pin "1") (pinfunction "1_1") (pintype "passive"))
      (node (ref "PS1") (pin "7") (pinfunction "+VOUT_7") (pintype "bidirectional"))
      (node (ref "PS4") (pin "4") (pinfunction "+VOUT_4") (pintype "bidirectional"))
      (node (ref "Q2") (pin "2") (pinfunction "C_2") (pintype "bidirectional"))
      (node (ref "Q4") (pin "2") (pinfunction "C_2") (pintype "bidirectional"))
      (node (ref "R14") (pin "2") (pinfunction "2_2") (pintype "passive"))
      (node (ref "R21") (pin "2") (pinfunction "2_2") (pintype "passive"))
    )
    (net (code "137") (name "VIN") (class "Default")
      (node (ref "C26") (pin "1") (pinfunction "1_1") (pintype "passive"))
      (node (ref "D2") (pin "P$1") (pinfunction "K_P$1") (pintype "bidirectional"))
      (node (ref "D3") (pin "K") (pinfunction "C_K") (pintype "passive"))
      (node (ref "IC14") (pin "1") (pinfunction "EN_1") (pintype "bidirectional"))
      (node (ref "IC14") (pin "2") (pinfunction "IN_2") (pintype "bidirectional"))
      (node (ref "JP6") (pin "8") (pinfunction "8_8") (pintype "passive"))
    )
    (net (code "138") (name "VIN+") (class "Default")
      (node (ref "J7") (pin "1") (pinfunction "1_1") (pintype "bidirectional"))
      (node (ref "L1") (pin "2") (pinfunction "2_2") (pintype "passive"))
    )
    (net (code "139") (name "VIN_5V") (class "Default")
      (node (ref "C13") (pin "1") (pinfunction "1_1") (pintype "passive"))
      (node (ref "C25") (pin "1") (pinfunction "1_1") (pintype "passive"))
      (node (ref "C29") (pin "+") (pinfunction "+_+") (pintype "passive"))
      (node (ref "D4") (pin "1") (pinfunction "K_1") (pintype "bidirectional"))
      (node (ref "D5") (pin "1") (pinfunction "K_1") (pintype "bidirectional"))
      (node (ref "IC13") (pin "1") (pinfunction "IN_1") (pintype "bidirectional"))
      (node (ref "IC13") (pin "3") (pinfunction "EN_3") (pintype "bidirectional"))
      (node (ref "K2") (pin "4") (pinfunction "LOAD+1_4") (pintype "bidirectional"))
      (node (ref "K2") (pin "6") (pinfunction "LOAD+_6") (pintype "bidirectional"))
      (node (ref "PS3") (pin "2") (pinfunction "+VIN_(VCC)_2") (pintype "bidirectional"))
      (node (ref "R33") (pin "1") (pinfunction "1_1") (pintype "passive"))
      (node (ref "U6") (pin "6") (pinfunction "SENSE_6") (pintype "input"))
      (node (ref "U7") (pin "2") (pinfunction "S_2") (pintype "passive"))
      (node (ref "VIN5V") (pin "TP") (pinfunction "TP_TP") (pintype "input"))
    )
    (net (code "140") (name "VSS") (class "Default")
      (node (ref "-HV") (pin "TP") (pinfunction "TP_TP") (pintype "input"))
      (node (ref "C31") (pin "2") (pinfunction "2_2") (pintype "passive"))
      (node (ref "C36") (pin "1") (pinfunction "1_1") (pintype "passive"))
      (node (ref "C38") (pin "1") (pinfunction "1_1") (pintype "passive"))
      (node (ref "PS6") (pin "3") (pinfunction "-VOUT_3") (pintype "bidirectional"))
      (node (ref "PS7") (pin "5") (pinfunction "-VOUT_5") (pintype "bidirectional"))
      (node (ref "Q1") (pin "2") (pinfunction "C_2") (pintype "bidirectional"))
      (node (ref "Q3") (pin "2") (pinfunction "C_2") (pintype "bidirectional"))
      (node (ref "R11") (pin "1") (pinfunction "1_1") (pintype "passive"))
      (node (ref "R18") (pin "1") (pinfunction "1_1") (pintype "passive"))
    )
    (net (code "141") (name "VSTIM1N") (class "Default")
      (node (ref "IC12") (pin "6") (pinfunction "VINB-_6") (pintype "bidirectional"))
      (node (ref "IC12") (pin "7") (pinfunction "VOUTB_7") (pintype "bidirectional"))
      (node (ref "IC5") (pin "2") (pinfunction "-IN_2") (pintype "input"))
      (node (ref "VSTIM1N") (pin "TP") (pinfunction "TP_TP") (pintype "input"))
    )
    (net (code "142") (name "VSTIM1P") (class "Default")
      (node (ref "IC12") (pin "1") (pinfunction "VOUTA_1") (pintype "bidirectional"))
      (node (ref "IC12") (pin "2") (pinfunction "VINA-_2") (pintype "bidirectional"))
      (node (ref "IC5") (pin "3") (pinfunction "+IN_3") (pintype "input"))
      (node (ref "VSTIM1P") (pin "TP") (pinfunction "TP_TP") (pintype "input"))
    )
    (net (code "143") (name "VSTIM2N") (class "Default")
      (node (ref "IC12") (pin "13") (pinfunction "VIND-_13") (pintype "bidirectional"))
      (node (ref "IC12") (pin "14") (pinfunction "V_OUTD_14") (pintype "bidirectional"))
      (node (ref "IC8") (pin "2") (pinfunction "-IN_2") (pintype "input"))
      (node (ref "VSTIM2N") (pin "TP") (pinfunction "TP_TP") (pintype "input"))
    )
    (net (code "144") (name "VSTIM2P") (class "Default")
      (node (ref "IC12") (pin "8") (pinfunction "V_OUTC_8") (pintype "bidirectional"))
      (node (ref "IC12") (pin "9") (pinfunction "VINC-_9") (pintype "bidirectional"))
      (node (ref "IC8") (pin "3") (pinfunction "+IN_3") (pintype "input"))
      (node (ref "VSTIM2P") (pin "TP") (pinfunction "TP_TP") (pintype "input"))
    )
    (net (code "145") (name "XVCC") (class "Default")
      (node (ref "F1") (pin "2") (pinfunction "2_2") (pintype "passive"))
      (node (ref "J2") (pin "1") (pinfunction "VBUS_1") (pintype "bidirectional"))
      (node (ref "TP3") (pin "X") (pinfunction "P$1_X") (pintype "passive"))
    )
    (net (code "146") (name "unconnected-(IC2-CBUS2-Pad13)") (class "Default")
      (node (ref "IC2") (pin "13") (pinfunction "CBUS2_13") (pintype "bidirectional"))
    )
    (net (code "147") (name "unconnected-(IC2-CBUS4-Pad12)") (class "Default")
      (node (ref "IC2") (pin "12") (pinfunction "CBUS4_12") (pintype "bidirectional"))
    )
    (net (code "148") (name "unconnected-(IC2-OSCI-Pad27)") (class "Default")
      (node (ref "IC2") (pin "27") (pinfunction "OSCI_27") (pintype "input"))
    )
    (net (code "149") (name "unconnected-(IC2-OSCO-Pad28)") (class "Default")
      (node (ref "IC2") (pin "28") (pinfunction "OSCO_28") (pintype "output"))
    )
    (net (code "150") (name "unconnected-(IC2-~{CTS}-Pad11)") (class "Default")
      (node (ref "IC2") (pin "11") (pinfunction "~{CTS}_11") (pintype "input"))
    )
    (net (code "151") (name "unconnected-(IC2-~{DCD}-Pad10)") (class "Default")
      (node (ref "IC2") (pin "10") (pinfunction "~{DCD}_10") (pintype "input"))
    )
    (net (code "152") (name "unconnected-(IC2-~{DSR}-Pad9)") (class "Default")
      (node (ref "IC2") (pin "9") (pinfunction "~{DSR}_9") (pintype "input"))
    )
    (net (code "153") (name "unconnected-(IC2-~{DTR}-Pad2)") (class "Default")
      (node (ref "IC2") (pin "2") (pinfunction "~{DTR}_2") (pintype "output"))
    )
    (net (code "154") (name "unconnected-(IC2-~{RESET}-Pad19)") (class "Default")
      (node (ref "IC2") (pin "19") (pinfunction "~{RESET}_19") (pintype "input"))
    )
    (net (code "155") (name "unconnected-(IC2-~{RI}-Pad6)") (class "Default")
      (node (ref "IC2") (pin "6") (pinfunction "~{RI}_6") (pintype "input"))
    )
    (net (code "156") (name "unconnected-(IC2-~{RTS}-Pad3)") (class "Default")
      (node (ref "IC2") (pin "3") (pinfunction "~{RTS}_3") (pintype "output"))
    )
    (net (code "157") (name "unconnected-(IC5-NC-Pad8)") (class "Default")
      (node (ref "IC5") (pin "8") (pinfunction "NC_8") (pintype "no_connect"))
    )
    (net (code "158") (name "unconnected-(IC7-NC-Pad1)") (class "Default")
      (node (ref "IC7") (pin "1") (pinfunction "NC_1") (pintype "no_connect"))
    )
    (net (code "159") (name "unconnected-(IC7-NC_1-Pad5)") (class "Default")
      (node (ref "IC7") (pin "5") (pinfunction "NC_1_5") (pintype "bidirectional"))
    )
    (net (code "160") (name "unconnected-(IC7-NC_2-Pad8)") (class "Default")
      (node (ref "IC7") (pin "8") (pinfunction "NC_2_8") (pintype "bidirectional"))
    )
    (net (code "161") (name "unconnected-(IC8-NC-Pad8)") (class "Default")
      (node (ref "IC8") (pin "8") (pinfunction "NC_8") (pintype "no_connect"))
    )
    (net (code "162") (name "unconnected-(IC10-NC-Pad1)") (class "Default")
      (node (ref "IC10") (pin "1") (pinfunction "NC_1") (pintype "no_connect"))
    )
    (net (code "163") (name "unconnected-(IC10-NC_1-Pad5)") (class "Default")
      (node (ref "IC10") (pin "5") (pinfunction "NC_1_5") (pintype "bidirectional"))
    )
    (net (code "164") (name "unconnected-(IC10-NC_2-Pad8)") (class "Default")
      (node (ref "IC10") (pin "8") (pinfunction "NC_2_8") (pintype "bidirectional"))
    )
    (net (code "165") (name "unconnected-(IC15-AN3{slash}CMP2B{slash}AINDX1{slash}CN5{slash}RB3-Pad13)") (class "Default")
      (node (ref "IC15") (pin "13") (pinfunction "AN3/CMP2B/AINDX1/CN5/RB3_13") (pintype "bidirectional"))
    )
    (net (code "166") (name "unconnected-(IC15-AN4{slash}CMP2C{slash}CMP3A{slash}AQEA1{slash}CN6{slash}RB4-Pad12)") (class "Default")
      (node (ref "IC15") (pin "12") (pinfunction "AN4/CMP2C/CMP3A/AQEA1/CN6/RB4_12") (pintype "bidirectional"))
    )
    (net (code "167") (name "unconnected-(IC15-AN5{slash}CMP3B{slash}AQEB1{slash}CN7{slash}RB5-Pad11)") (class "Default")
      (node (ref "IC15") (pin "11") (pinfunction "AN5/CMP3B/AQEB1/CN7/RB5_11") (pintype "bidirectional"))
    )
    (net (code "168") (name "unconnected-(IC15-AN8{slash}~{U2CTS}{slash}RB8-Pad21)") (class "Default")
      (node (ref "IC15") (pin "21") (pinfunction "AN8/~{U2CTS}/RB8_21") (pintype "bidirectional"))
    )
    (net (code "169") (name "unconnected-(IC15-C1TX{slash}RF1-Pad59)") (class "Default")
      (node (ref "IC15") (pin "59") (pinfunction "C1TX/RF1_59") (pintype "bidirectional"))
    )
    (net (code "170") (name "unconnected-(IC15-OSC1{slash}CLKIN{slash}RC12-Pad39)") (class "Default")
      (node (ref "IC15") (pin "39") (pinfunction "OSC1/CLKIN/RC12_39") (pintype "bidirectional"))
    )
    (net (code "171") (name "unconnected-(IC15-PWM1H{slash}RE1-Pad61)") (class "Default")
      (node (ref "IC15") (pin "61") (pinfunction "PWM1H/RE1_61") (pintype "bidirectional"))
    )
    (net (code "172") (name "unconnected-(IC15-PWM2H{slash}RE3-Pad63)") (class "Default")
      (node (ref "IC15") (pin "63") (pinfunction "PWM2H/RE3_63") (pintype "bidirectional"))
    )
    (net (code "173") (name "unconnected-(IC15-PWM3H{slash}RE5-Pad1)") (class "Default")
      (node (ref "IC15") (pin "1") (pinfunction "PWM3H/RE5_1") (pintype "bidirectional"))
    )
    (net (code "174") (name "unconnected-(IC15-PWM4H{slash}RE7-Pad3)") (class "Default")
      (node (ref "IC15") (pin "3") (pinfunction "PWM4H/RE7_3") (pintype "bidirectional"))
    )
    (net (code "175") (name "unconnected-(IC15-PWM4L{slash}RE6-Pad2)") (class "Default")
      (node (ref "IC15") (pin "2") (pinfunction "PWM4L/RE6_2") (pintype "bidirectional"))
    )
    (net (code "176") (name "unconnected-(IC15-PWM5H{slash}UPDN1{slash}CN16{slash}RD7-Pad55)") (class "Default")
      (node (ref "IC15") (pin "55") (pinfunction "PWM5H/UPDN1/CN16/RD7_55") (pintype "bidirectional"))
    )
    (net (code "177") (name "unconnected-(IC15-PWM5L{slash}CN15{slash}RD6-Pad54)") (class "Default")
      (node (ref "IC15") (pin "54") (pinfunction "PWM5L/CN15/RD6_54") (pintype "bidirectional"))
    )
    (net (code "178") (name "unconnected-(IC15-TDO{slash}AN11{slash}EXTREF{slash}RB11-Pad24)") (class "Default")
      (node (ref "IC15") (pin "24") (pinfunction "TDO/AN11/EXTREF/RB11_24") (pintype "bidirectional"))
    )
    (net (code "179") (name "unconnected-(IC15-TMS{slash}AN10{slash}INDX2{slash}RB10-Pad23)") (class "Default")
      (node (ref "IC15") (pin "23") (pinfunction "TMS/AN10/INDX2/RB10_23") (pintype "bidirectional"))
    )
    (net (code "180") (name "unconnected-(J2-ID-Pad4)") (class "Default")
      (node (ref "J2") (pin "4") (pinfunction "ID_4") (pintype "bidirectional"))
    )
    (net (code "181") (name "unconnected-(JP2-Pad2)") (class "Default")
      (node (ref "JP2") (pin "2") (pinfunction "2_2") (pintype "passive"))
    )
    (net (code "182") (name "unconnected-(JP6-Pad1)") (class "Default")
      (node (ref "JP6") (pin "1") (pinfunction "1_1") (pintype "passive"))
    )
    (net (code "183") (name "unconnected-(JP6-Pad2)") (class "Default")
      (node (ref "JP6") (pin "2") (pinfunction "2_2") (pintype "passive"))
    )
    (net (code "184") (name "unconnected-(JP6-Pad4)") (class "Default")
      (node (ref "JP6") (pin "4") (pinfunction "4_4") (pintype "passive"))
    )
    (net (code "185") (name "unconnected-(K2-DO_NOT_USE_1-Pad3)") (class "Default")
      (node (ref "K2") (pin "3") (pinfunction "DO_NOT_USE_1_3") (pintype "bidirectional"))
    )
    (net (code "186") (name "unconnected-(PS1-0V-Pad6)") (class "Default")
      (node (ref "PS1") (pin "6") (pinfunction "0V_6") (pintype "bidirectional"))
    )
    (net (code "187") (name "unconnected-(PS4-0V-Pad5)") (class "Default")
      (node (ref "PS4") (pin "5") (pinfunction "0V_5") (pintype "bidirectional"))
    )
    (net (code "188") (name "unconnected-(PS4-NC-Pad6)") (class "Default")
      (node (ref "PS4") (pin "6") (pinfunction "NC_6") (pintype "bidirectional"))
    )
    (net (code "189") (name "unconnected-(PS5-NC-Pad6)") (class "Default")
      (node (ref "PS5") (pin "6") (pinfunction "NC_6") (pintype "bidirectional"))
    )
    (net (code "190") (name "unconnected-(PS6-0V-Pad5)") (class "Default")
      (node (ref "PS6") (pin "5") (pinfunction "0V_5") (pintype "bidirectional"))
    )
    (net (code "191") (name "unconnected-(PS6-NC-Pad6)") (class "Default")
      (node (ref "PS6") (pin "6") (pinfunction "NC_6") (pintype "bidirectional"))
    )
    (net (code "192") (name "unconnected-(PS7-0V-Pad6)") (class "Default")
      (node (ref "PS7") (pin "6") (pinfunction "0V_6") (pintype "bidirectional"))
    )
    (net (code "193") (name "~{HV_ENABLE}") (class "Default")
      (node (ref "IC15") (pin "45") (pinfunction "IC4/QEA1/FLT4/INT4/RD11_45") (pintype "bidirectional"))
      (node (ref "R31") (pin "1") (pinfunction "1_1") (pintype "passive"))
    )
  )
)
